# rizon-smd.net
KiCad netlist of a schematic drawn in EAGLE
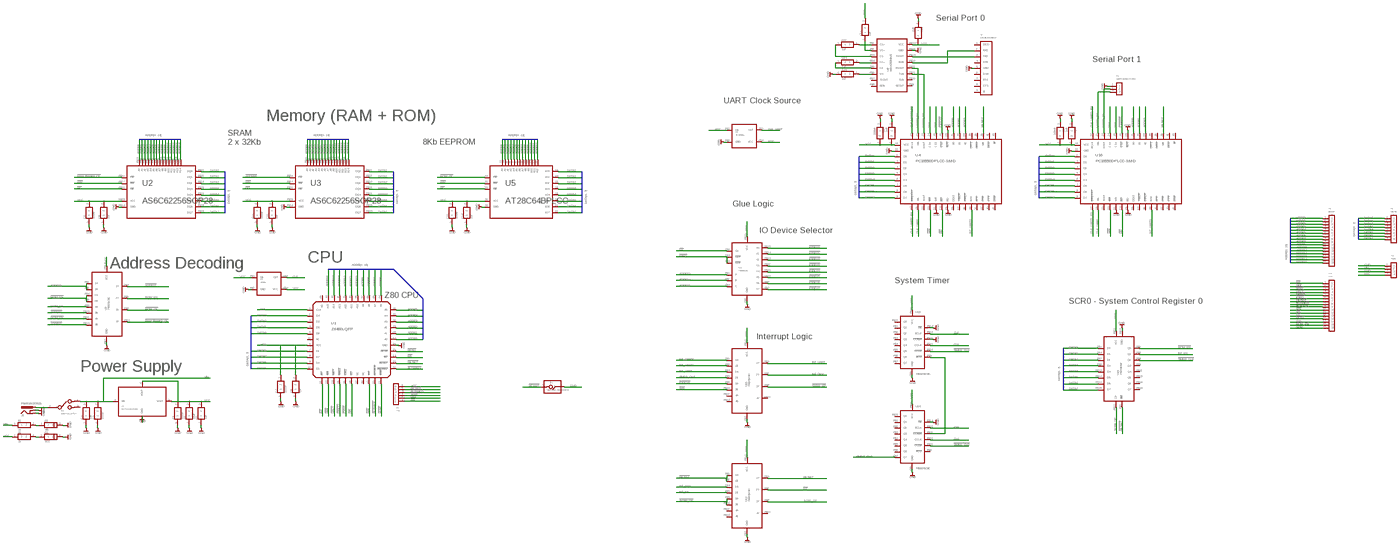
[diagram p0: schematic, sheet 1, overview]
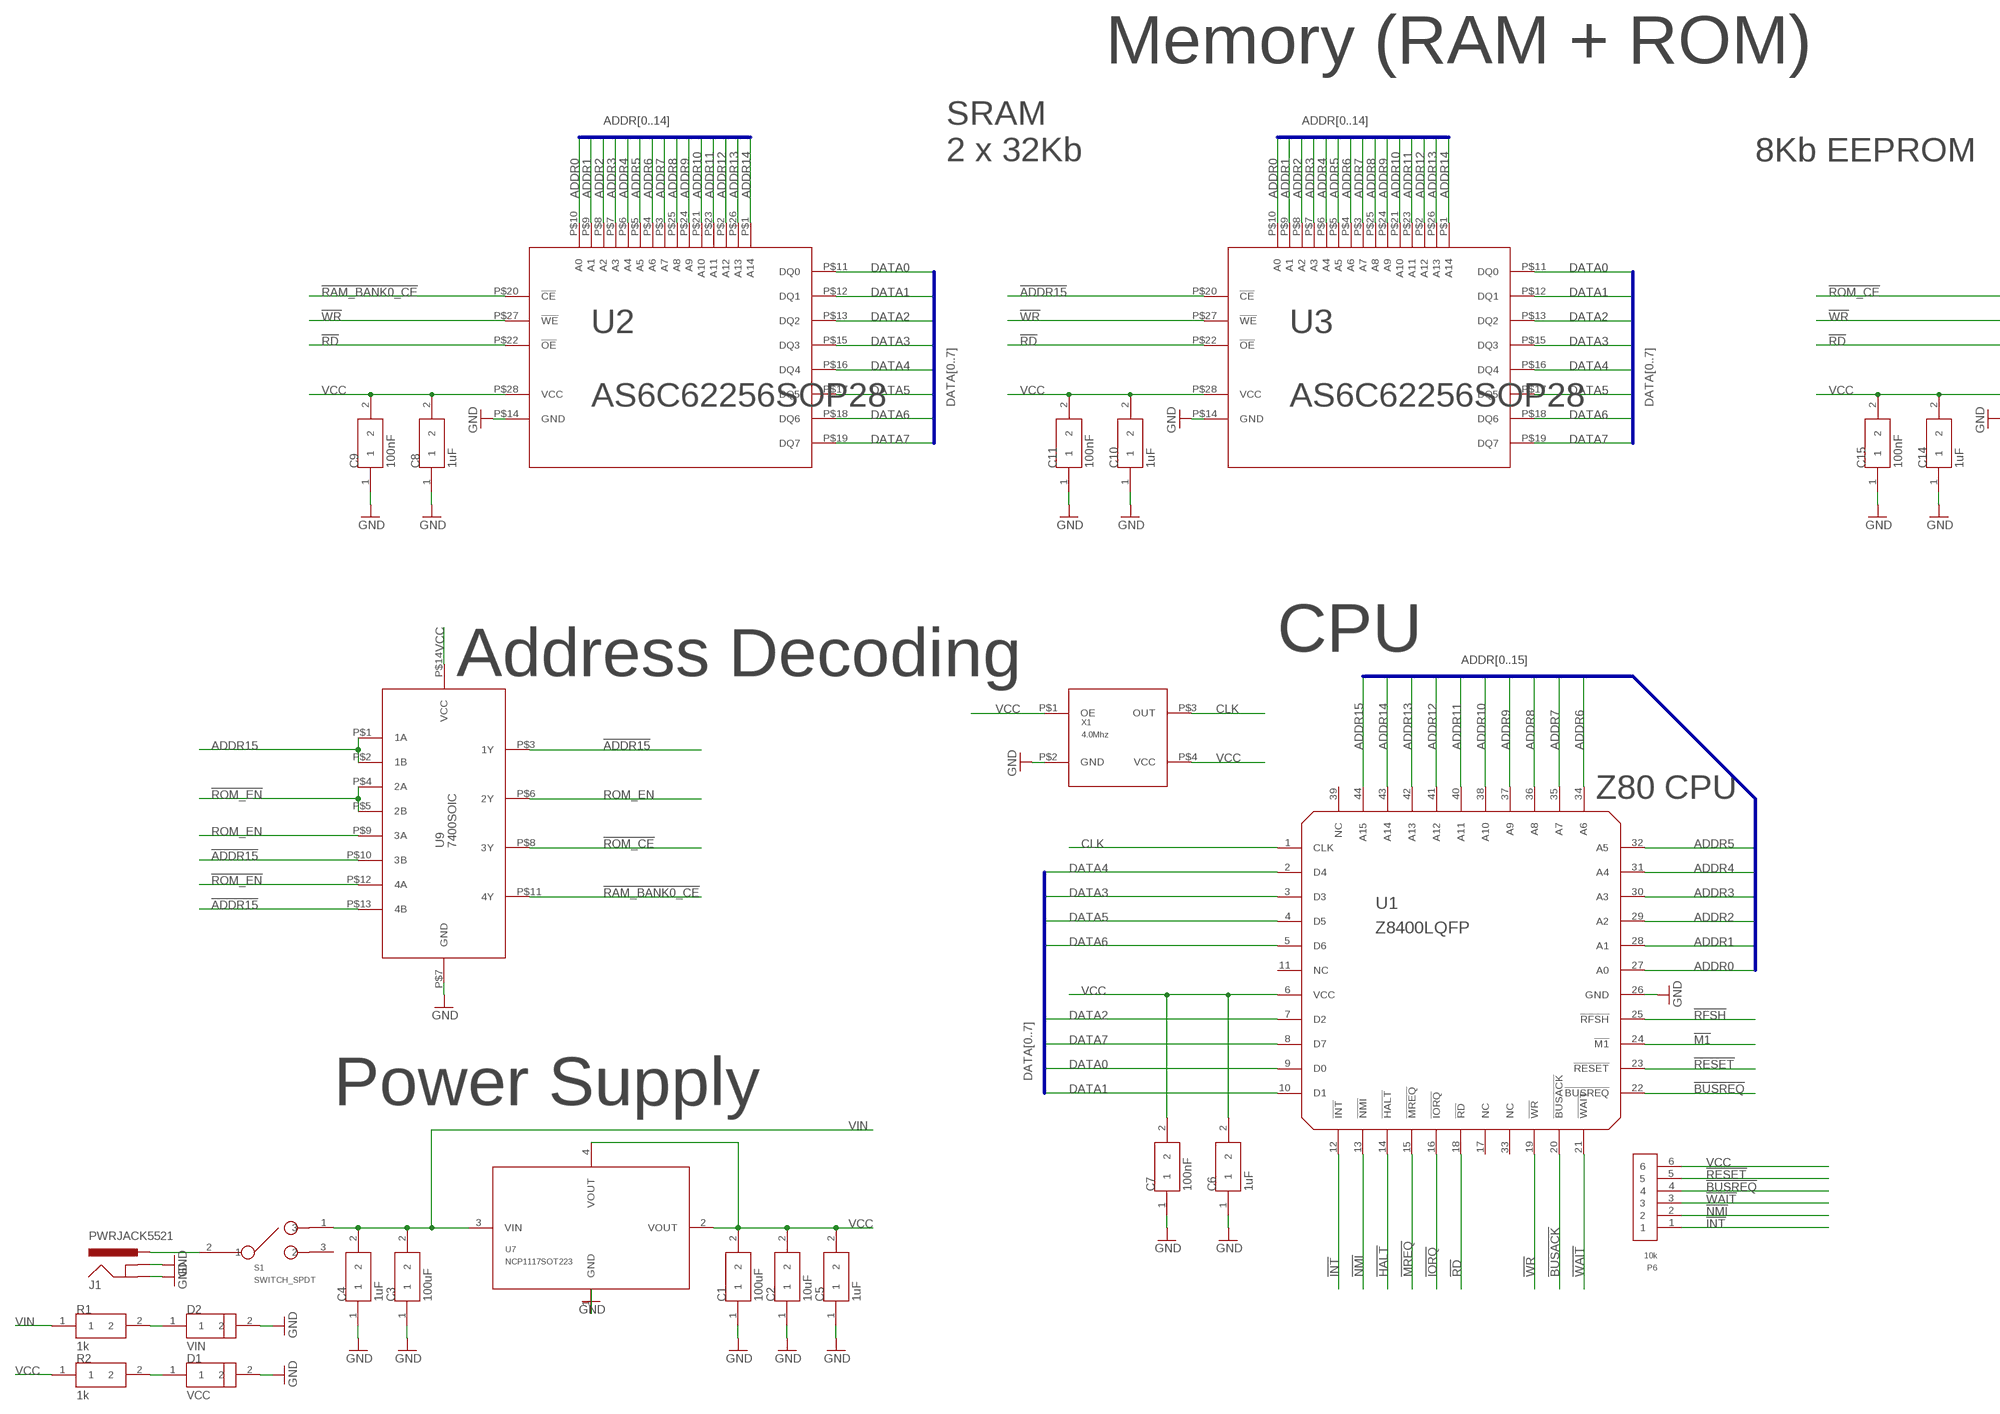
[diagram p1: schematic, sheet 1, part 1 of 4]
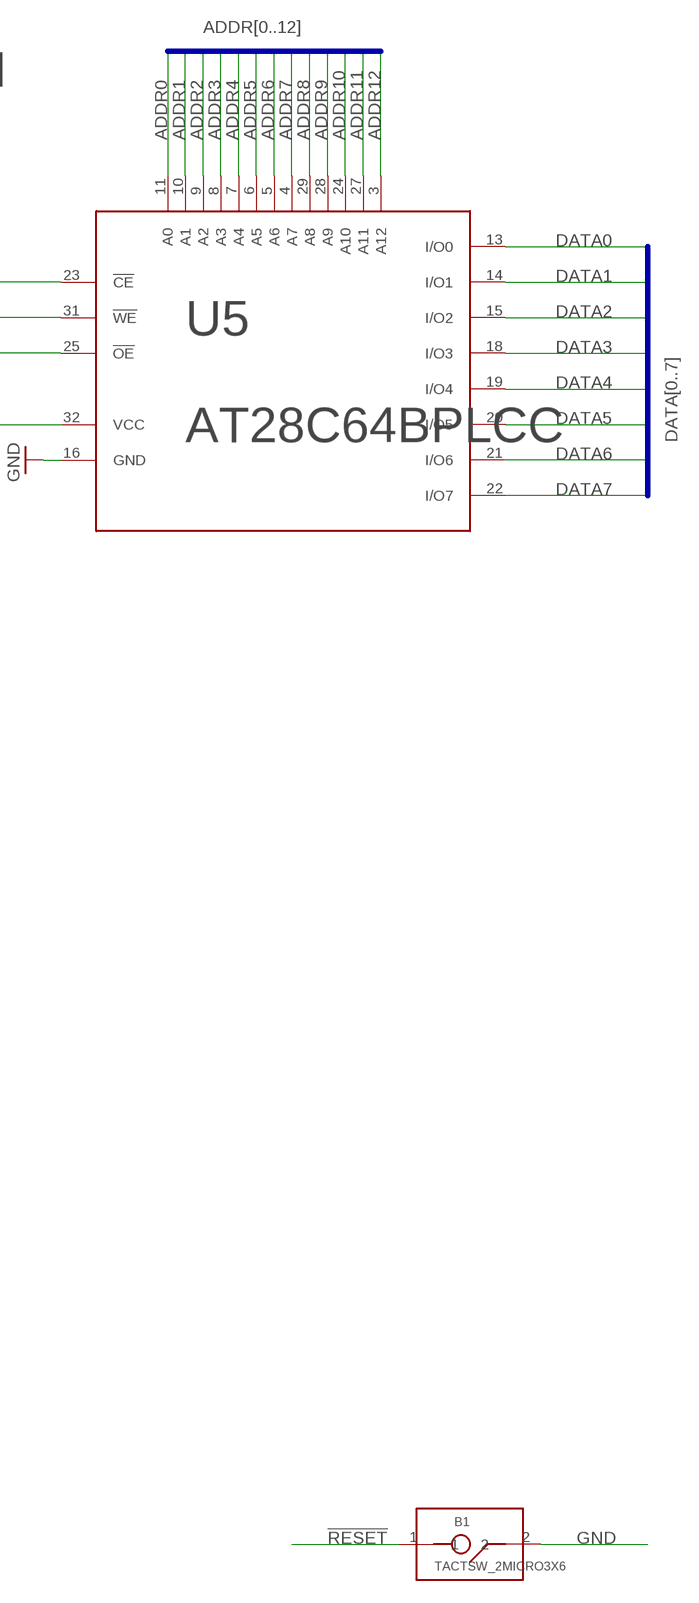
[diagram p2: schematic, sheet 1, part 2 of 4]
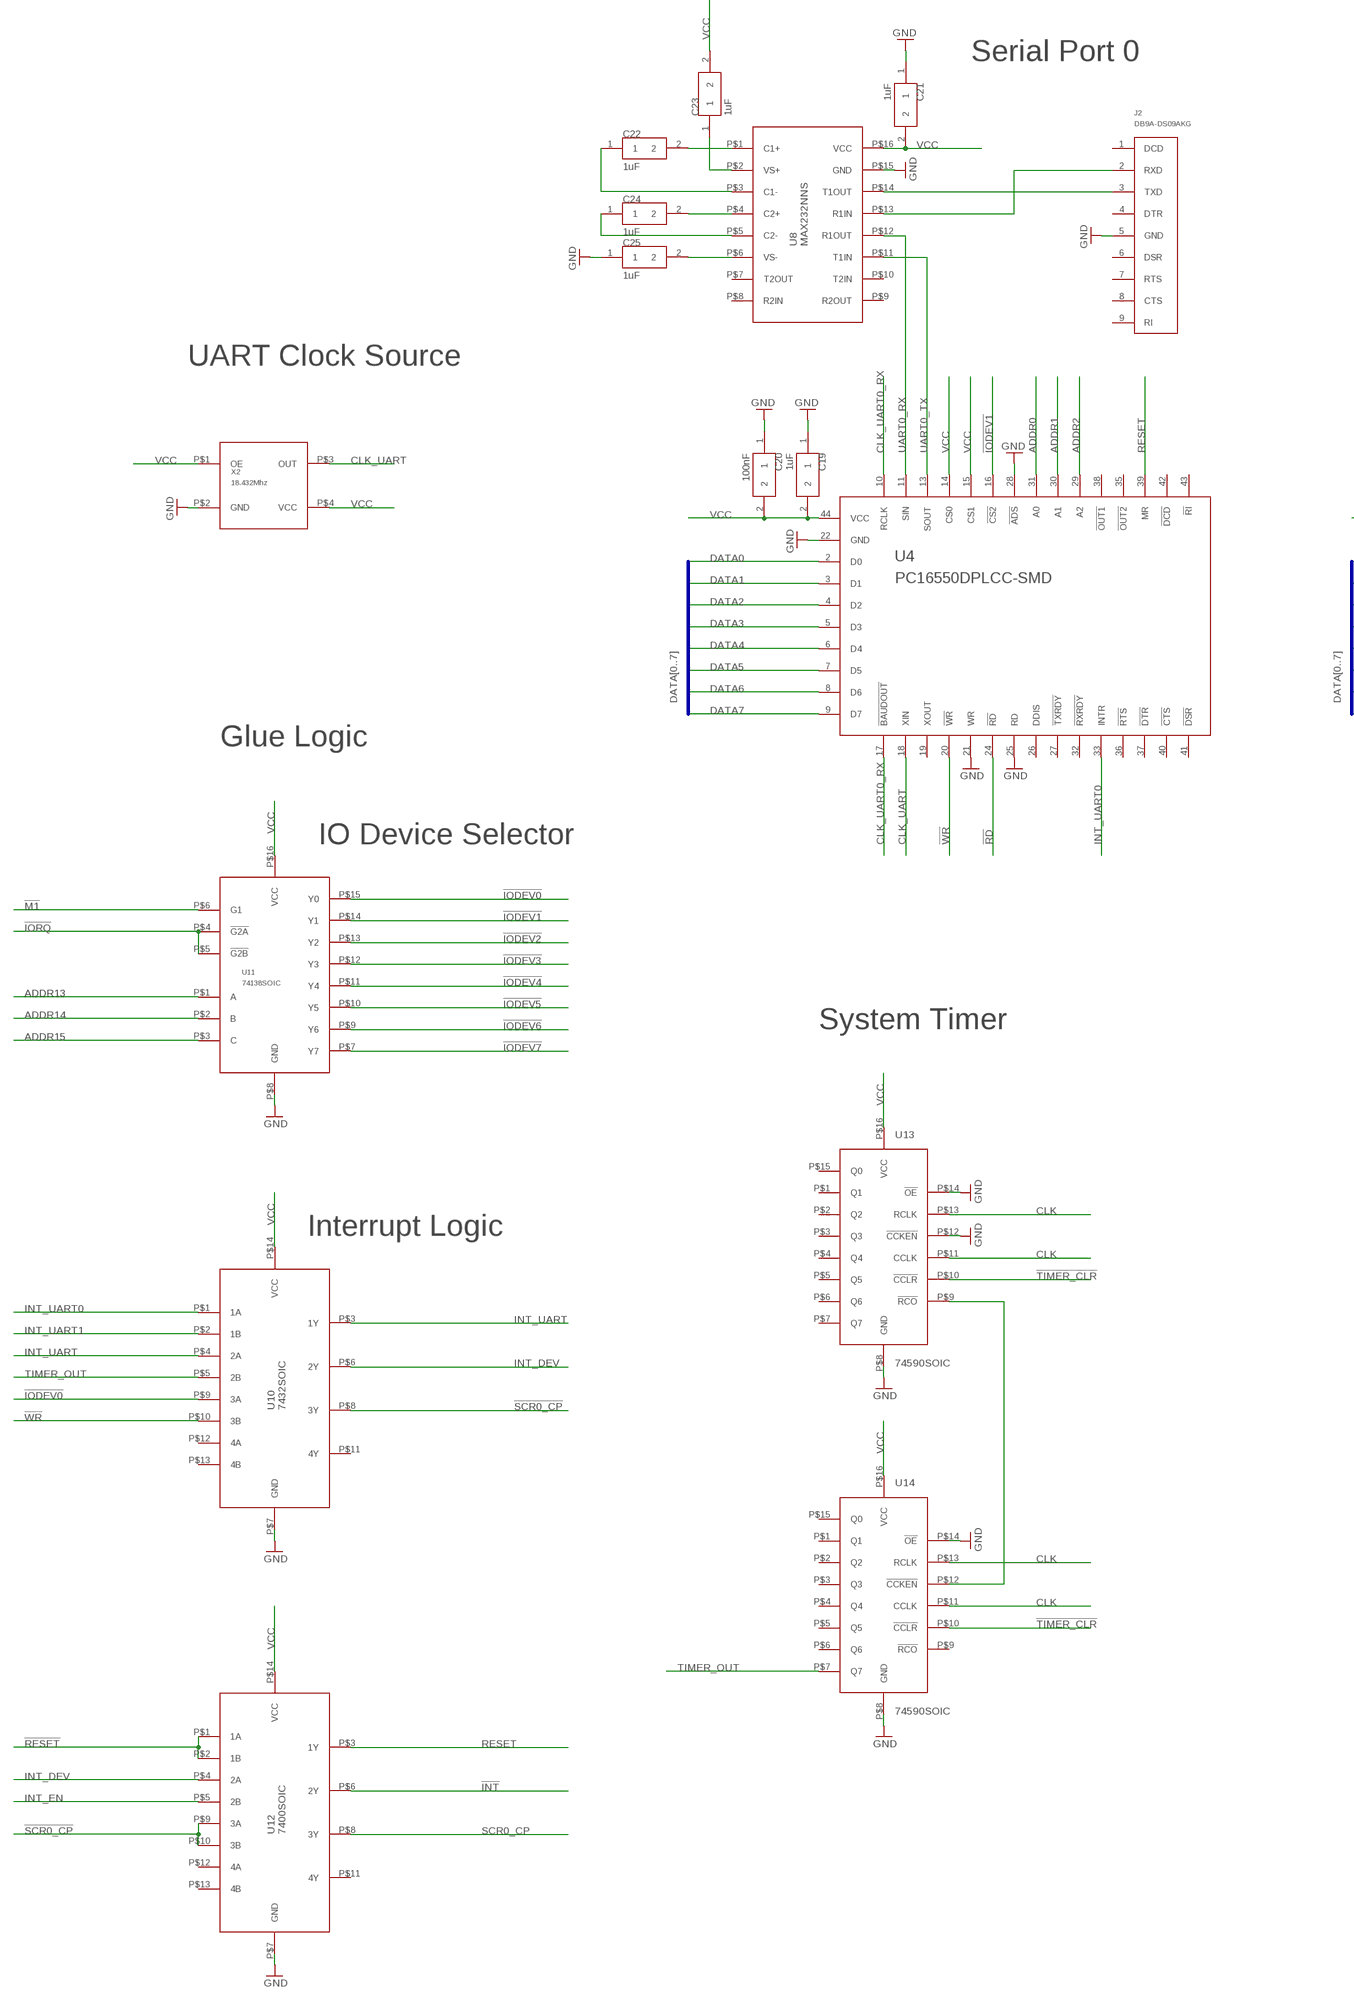
[diagram p3: schematic, sheet 1, part 3 of 4]
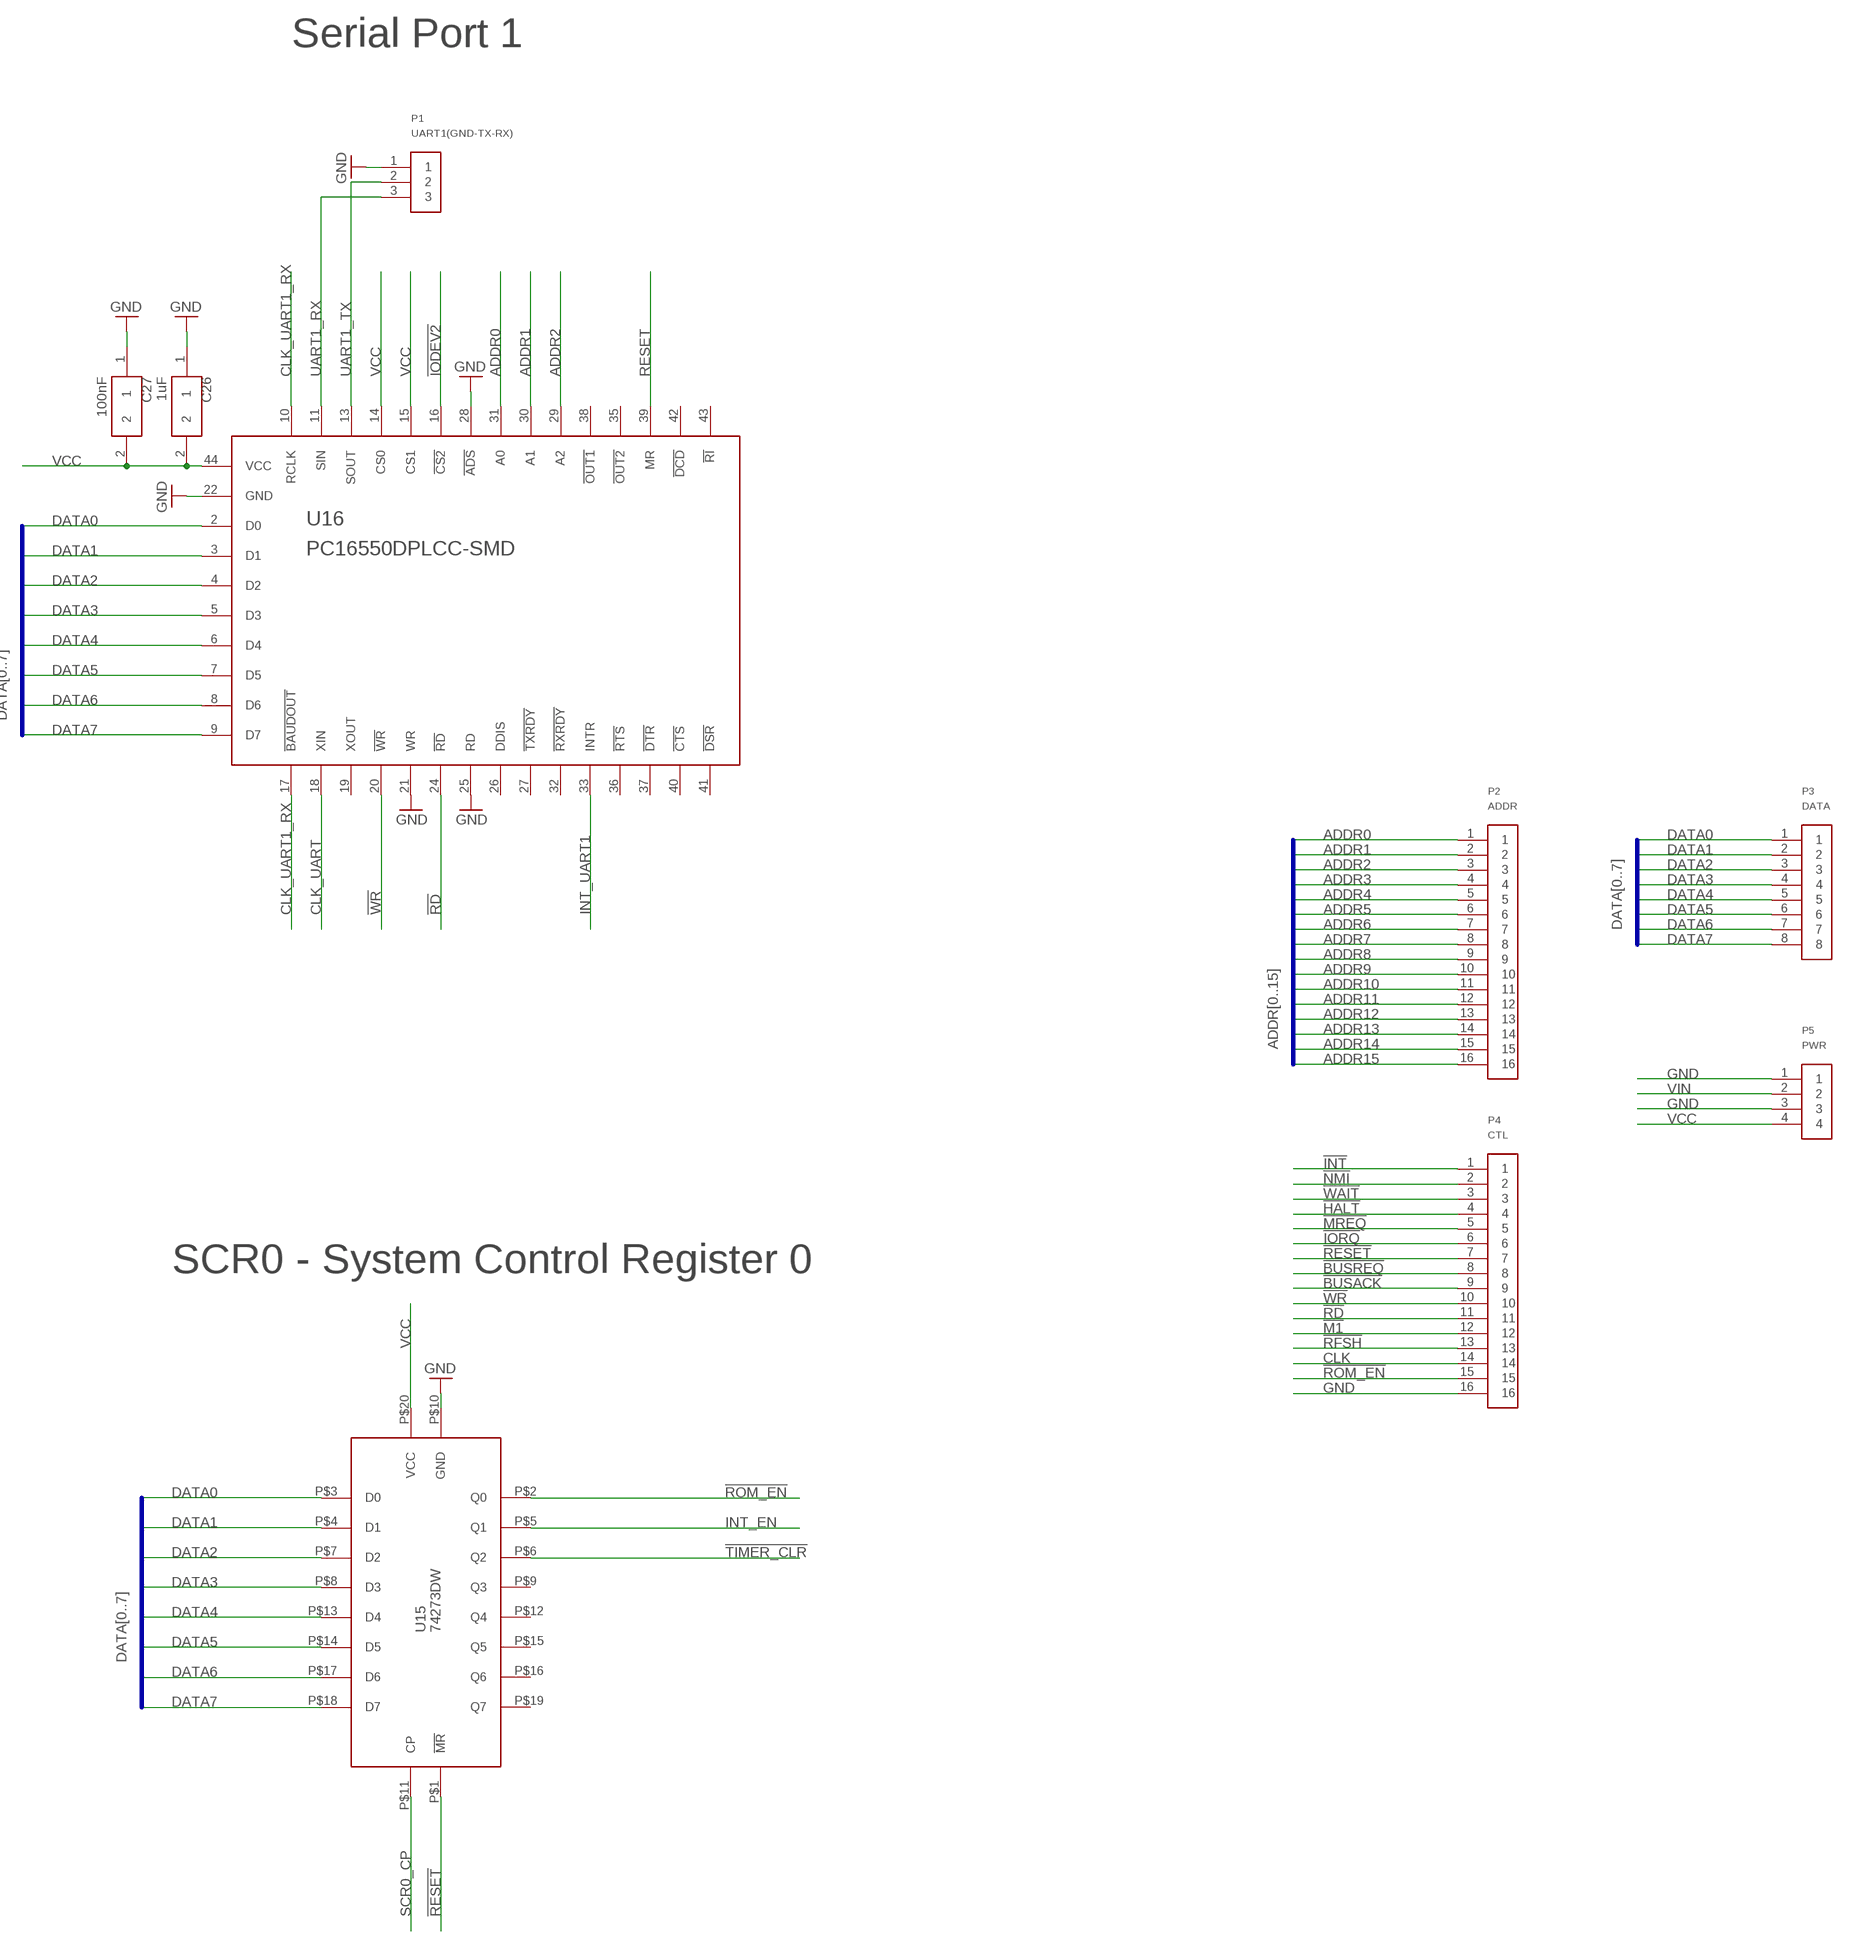
[diagram p4: schematic, sheet 1, part 4 of 4]

(export (version "E")
  (design (tool "Eeschema 10.0.6"))
  (components
    (comp (ref "B1")
      (value "TACTSW_2MICRO3X6")
      (footprint "eagle-import:TACTSW_MICRO3X6")
      (libsource (lib "eagle-import") (part "TACTSW_2MICRO3X6"))
    )
    (comp (ref "C1")
      (value "100uF")
      (footprint "eagle-import:1210")
      (libsource (lib "eagle-import") (part "CAP1210"))
    )
    (comp (ref "C2")
      (value "10uF")
      (footprint "eagle-import:0805")
      (libsource (lib "eagle-import") (part "CAP0805"))
    )
    (comp (ref "C3")
      (value "100uF")
      (footprint "eagle-import:1210")
      (libsource (lib "eagle-import") (part "CAP1210"))
    )
    (comp (ref "C4")
      (value "1uF")
      (footprint "eagle-import:0805")
      (libsource (lib "eagle-import") (part "CAP0805"))
    )
    (comp (ref "C5")
      (value "1uF")
      (footprint "eagle-import:0805")
      (libsource (lib "eagle-import") (part "CAP0805"))
    )
    (comp (ref "C6")
      (value "1uF")
      (footprint "eagle-import:0805")
      (libsource (lib "eagle-import") (part "CAP0805"))
    )
    (comp (ref "C7")
      (value "100nF")
      (footprint "eagle-import:0805")
      (libsource (lib "eagle-import") (part "CAP0805"))
    )
    (comp (ref "C8")
      (value "1uF")
      (footprint "eagle-import:0805")
      (libsource (lib "eagle-import") (part "CAP0805"))
    )
    (comp (ref "C9")
      (value "100nF")
      (footprint "eagle-import:0805")
      (libsource (lib "eagle-import") (part "CAP0805"))
    )
    (comp (ref "C10")
      (value "1uF")
      (footprint "eagle-import:0805")
      (libsource (lib "eagle-import") (part "CAP0805"))
    )
    (comp (ref "C11")
      (value "100nF")
      (footprint "eagle-import:0805")
      (libsource (lib "eagle-import") (part "CAP0805"))
    )
    (comp (ref "C14")
      (value "1uF")
      (footprint "eagle-import:0805")
      (libsource (lib "eagle-import") (part "CAP0805"))
    )
    (comp (ref "C15")
      (value "100nF")
      (footprint "eagle-import:0805")
      (libsource (lib "eagle-import") (part "CAP0805"))
    )
    (comp (ref "C19")
      (value "1uF")
      (footprint "eagle-import:0805")
      (libsource (lib "eagle-import") (part "CAP0805"))
    )
    (comp (ref "C20")
      (value "100nF")
      (footprint "eagle-import:0805")
      (libsource (lib "eagle-import") (part "CAP0805"))
    )
    (comp (ref "C21")
      (value "1uF")
      (footprint "eagle-import:0805")
      (libsource (lib "eagle-import") (part "CAP0805"))
    )
    (comp (ref "C22")
      (value "1uF")
      (footprint "eagle-import:0805")
      (libsource (lib "eagle-import") (part "CAP0805"))
    )
    (comp (ref "C23")
      (value "1uF")
      (footprint "eagle-import:0805")
      (libsource (lib "eagle-import") (part "CAP0805"))
    )
    (comp (ref "C24")
      (value "1uF")
      (footprint "eagle-import:0805")
      (libsource (lib "eagle-import") (part "CAP0805"))
    )
    (comp (ref "C25")
      (value "1uF")
      (footprint "eagle-import:0805")
      (libsource (lib "eagle-import") (part "CAP0805"))
    )
    (comp (ref "C26")
      (value "1uF")
      (footprint "eagle-import:0805")
      (libsource (lib "eagle-import") (part "CAP0805"))
    )
    (comp (ref "C27")
      (value "100nF")
      (footprint "eagle-import:0805")
      (libsource (lib "eagle-import") (part "CAP0805"))
    )
    (comp (ref "D1")
      (value "VCC")
      (footprint "eagle-import:0805")
      (libsource (lib "eagle-import") (part "LED0805"))
    )
    (comp (ref "D2")
      (value "VIN")
      (footprint "eagle-import:0805")
      (libsource (lib "eagle-import") (part "LED0805"))
    )
    (comp (ref "J1")
      (value "PWRJACK5521")
      (footprint "eagle-import:PWRJACK_5521")
      (libsource (lib "eagle-import") (part "PWRJACK5521"))
    )
    (comp (ref "J2")
      (value "DB9A-DS09AKG")
      (footprint "eagle-import:A-DS09AKG")
      (libsource (lib "eagle-import") (part "DB9A-DS09AKG"))
    )
    (comp (ref "P1")
      (value "UART1(GND-TX-RX)")
      (footprint "eagle-import:PIN_3")
      (libsource (lib "eagle-import") (part "PIN_3"))
    )
    (comp (ref "P2")
      (value "ADDR")
      (footprint "eagle-import:PIN_16")
      (libsource (lib "eagle-import") (part "PIN_16"))
    )
    (comp (ref "P3")
      (value "DATA")
      (footprint "eagle-import:PIN_8")
      (libsource (lib "eagle-import") (part "PIN_8"))
    )
    (comp (ref "P4")
      (value "CTL")
      (footprint "eagle-import:PIN_16")
      (libsource (lib "eagle-import") (part "PIN_16"))
    )
    (comp (ref "P5")
      (value "PWR")
      (footprint "eagle-import:PIN_4")
      (libsource (lib "eagle-import") (part "PIN_4"))
    )
    (comp (ref "P6")
      (value "10k")
      (footprint "eagle-import:PIN_6")
      (libsource (lib "eagle-import") (part "PIN_61LINE"))
    )
    (comp (ref "R1")
      (value "1k")
      (footprint "eagle-import:0805")
      (libsource (lib "eagle-import") (part "RES0805"))
    )
    (comp (ref "R2")
      (value "1k")
      (footprint "eagle-import:0805")
      (libsource (lib "eagle-import") (part "RES0805"))
    )
    (comp (ref "S1")
      (value "SWITCH_SPDT")
      (footprint "eagle-import:JS102011")
      (libsource (lib "eagle-import") (part "SWITCH_SPDT"))
    )
    (comp (ref "U1")
      (value "Z8400LQFP")
      (footprint "eagle-import:QFP44")
      (libsource (lib "eagle-import") (part "Z8400LQFP"))
    )
    (comp (ref "U2")
      (value "AS6C62256SOP28")
      (footprint "eagle-import:SOP28")
      (libsource (lib "eagle-import") (part "AS6C62256SOP28"))
    )
    (comp (ref "U3")
      (value "AS6C62256SOP28")
      (footprint "eagle-import:SOP28")
      (libsource (lib "eagle-import") (part "AS6C62256SOP28"))
    )
    (comp (ref "U4")
      (value "PC16550DPLCC-SMD")
      (footprint "eagle-import:PLCC44")
      (libsource (lib "eagle-import") (part "PC16550DPLCC-SMD"))
    )
    (comp (ref "U5")
      (value "AT28C64BPLCC")
      (footprint "eagle-import:PLCC-S32--SOCKET")
      (libsource (lib "eagle-import") (part "AT28C64BPLCC"))
    )
    (comp (ref "U7")
      (value "NCP1117SOT223")
      (footprint "eagle-import:SOT223")
      (libsource (lib "eagle-import") (part "NCP1117SOT223"))
    )
    (comp (ref "U8")
      (value "MAX232NNS")
      (footprint "eagle-import:SO16")
      (libsource (lib "eagle-import") (part "MAX232NNS"))
    )
    (comp (ref "U9")
      (value "7400SOIC")
      (footprint "eagle-import:SOIC14")
      (libsource (lib "eagle-import") (part "7400SOIC"))
    )
    (comp (ref "U10")
      (value "7432SOIC")
      (footprint "eagle-import:SOIC14")
      (libsource (lib "eagle-import") (part "7432SOIC"))
    )
    (comp (ref "U11")
      (value "74138SOIC")
      (footprint "eagle-import:SOIC16")
      (libsource (lib "eagle-import") (part "74138SOIC"))
    )
    (comp (ref "U12")
      (value "7400SOIC")
      (footprint "eagle-import:SOIC14")
      (libsource (lib "eagle-import") (part "7400SOIC"))
    )
    (comp (ref "U13")
      (value "74590SOIC")
      (footprint "eagle-import:SOIC16")
      (libsource (lib "eagle-import") (part "74590SOIC"))
    )
    (comp (ref "U14")
      (value "74590SOIC")
      (footprint "eagle-import:SOIC16")
      (libsource (lib "eagle-import") (part "74590SOIC"))
    )
    (comp (ref "U15")
      (value "74273DW")
      (footprint "eagle-import:SO20")
      (libsource (lib "eagle-import") (part "74273DW"))
    )
    (comp (ref "U16")
      (value "PC16550DPLCC-SMD")
      (footprint "eagle-import:PLCC44")
      (libsource (lib "eagle-import") (part "PC16550DPLCC-SMD"))
    )
    (comp (ref "X1")
      (value "4.0Mhz")
      (footprint "eagle-import:OSC4-SMD-7X5")
      (libsource (lib "eagle-import") (part "OSC4_OESMD-7X5"))
    )
    (comp (ref "X2")
      (value "18.432Mhz")
      (footprint "eagle-import:OSC4-SMD-7X5")
      (libsource (lib "eagle-import") (part "OSC4_OESMD-7X5"))
    )
  )
  (nets
    (net (code "1") (name "/ADDR0") (class "Default")
      (node (ref "P2") (pin "1") (pinfunction "1_1") (pintype "bidirectional"))
      (node (ref "U1") (pin "27") (pinfunction "A0_27") (pintype "bidirectional"))
      (node (ref "U16") (pin "31") (pinfunction "A0_31") (pintype "bidirectional"))
      (node (ref "U2") (pin "P$10") (pinfunction "A0_P$10") (pintype "bidirectional"))
      (node (ref "U3") (pin "P$10") (pinfunction "A0_P$10") (pintype "bidirectional"))
      (node (ref "U4") (pin "31") (pinfunction "A0_31") (pintype "bidirectional"))
      (node (ref "U5") (pin "11") (pinfunction "A0_11") (pintype "bidirectional"))
    )
    (net (code "2") (name "/ADDR1") (class "Default")
      (node (ref "P2") (pin "2") (pinfunction "2_2") (pintype "bidirectional"))
      (node (ref "U1") (pin "28") (pinfunction "A1_28") (pintype "bidirectional"))
      (node (ref "U16") (pin "30") (pinfunction "A1_30") (pintype "bidirectional"))
      (node (ref "U2") (pin "P$9") (pinfunction "A1_P$9") (pintype "bidirectional"))
      (node (ref "U3") (pin "P$9") (pinfunction "A1_P$9") (pintype "bidirectional"))
      (node (ref "U4") (pin "30") (pinfunction "A1_30") (pintype "bidirectional"))
      (node (ref "U5") (pin "10") (pinfunction "A1_10") (pintype "bidirectional"))
    )
    (net (code "3") (name "/ADDR2") (class "Default")
      (node (ref "P2") (pin "3") (pinfunction "3_3") (pintype "bidirectional"))
      (node (ref "U1") (pin "29") (pinfunction "A2_29") (pintype "bidirectional"))
      (node (ref "U16") (pin "29") (pinfunction "A2_29") (pintype "bidirectional"))
      (node (ref "U2") (pin "P$8") (pinfunction "A2_P$8") (pintype "bidirectional"))
      (node (ref "U3") (pin "P$8") (pinfunction "A2_P$8") (pintype "bidirectional"))
      (node (ref "U4") (pin "29") (pinfunction "A2_29") (pintype "bidirectional"))
      (node (ref "U5") (pin "9") (pinfunction "A2_9") (pintype "bidirectional"))
    )
    (net (code "4") (name "/ADDR3") (class "Default")
      (node (ref "P2") (pin "4") (pinfunction "4_4") (pintype "bidirectional"))
      (node (ref "U1") (pin "30") (pinfunction "A3_30") (pintype "bidirectional"))
      (node (ref "U2") (pin "P$7") (pinfunction "A3_P$7") (pintype "bidirectional"))
      (node (ref "U3") (pin "P$7") (pinfunction "A3_P$7") (pintype "bidirectional"))
      (node (ref "U5") (pin "8") (pinfunction "A3_8") (pintype "bidirectional"))
    )
    (net (code "5") (name "/ADDR4") (class "Default")
      (node (ref "P2") (pin "5") (pinfunction "5_5") (pintype "bidirectional"))
      (node (ref "U1") (pin "31") (pinfunction "A4_31") (pintype "bidirectional"))
      (node (ref "U2") (pin "P$6") (pinfunction "A4_P$6") (pintype "bidirectional"))
      (node (ref "U3") (pin "P$6") (pinfunction "A4_P$6") (pintype "bidirectional"))
      (node (ref "U5") (pin "7") (pinfunction "A4_7") (pintype "bidirectional"))
    )
    (net (code "6") (name "/ADDR5") (class "Default")
      (node (ref "P2") (pin "6") (pinfunction "6_6") (pintype "bidirectional"))
      (node (ref "U1") (pin "32") (pinfunction "A5_32") (pintype "bidirectional"))
      (node (ref "U2") (pin "P$5") (pinfunction "A5_P$5") (pintype "bidirectional"))
      (node (ref "U3") (pin "P$5") (pinfunction "A5_P$5") (pintype "bidirectional"))
      (node (ref "U5") (pin "6") (pinfunction "A5_6") (pintype "bidirectional"))
    )
    (net (code "7") (name "/ADDR6") (class "Default")
      (node (ref "P2") (pin "7") (pinfunction "7_7") (pintype "bidirectional"))
      (node (ref "U1") (pin "34") (pinfunction "A6_34") (pintype "bidirectional"))
      (node (ref "U2") (pin "P$4") (pinfunction "A6_P$4") (pintype "bidirectional"))
      (node (ref "U3") (pin "P$4") (pinfunction "A6_P$4") (pintype "bidirectional"))
      (node (ref "U5") (pin "5") (pinfunction "A6_5") (pintype "bidirectional"))
    )
    (net (code "8") (name "/ADDR7") (class "Default")
      (node (ref "P2") (pin "8") (pinfunction "8_8") (pintype "bidirectional"))
      (node (ref "U1") (pin "35") (pinfunction "A7_35") (pintype "bidirectional"))
      (node (ref "U2") (pin "P$3") (pinfunction "A7_P$3") (pintype "bidirectional"))
      (node (ref "U3") (pin "P$3") (pinfunction "A7_P$3") (pintype "bidirectional"))
      (node (ref "U5") (pin "4") (pinfunction "A7_4") (pintype "bidirectional"))
    )
    (net (code "9") (name "/ADDR8") (class "Default")
      (node (ref "P2") (pin "9") (pinfunction "9_9") (pintype "bidirectional"))
      (node (ref "U1") (pin "36") (pinfunction "A8_36") (pintype "bidirectional"))
      (node (ref "U2") (pin "P$25") (pinfunction "A8_P$25") (pintype "bidirectional"))
      (node (ref "U3") (pin "P$25") (pinfunction "A8_P$25") (pintype "bidirectional"))
      (node (ref "U5") (pin "29") (pinfunction "A8_29") (pintype "bidirectional"))
    )
    (net (code "10") (name "/ADDR9") (class "Default")
      (node (ref "P2") (pin "10") (pinfunction "10_10") (pintype "bidirectional"))
      (node (ref "U1") (pin "37") (pinfunction "A9_37") (pintype "bidirectional"))
      (node (ref "U2") (pin "P$24") (pinfunction "A9_P$24") (pintype "bidirectional"))
      (node (ref "U3") (pin "P$24") (pinfunction "A9_P$24") (pintype "bidirectional"))
      (node (ref "U5") (pin "28") (pinfunction "A9_28") (pintype "bidirectional"))
    )
    (net (code "11") (name "/ADDR10") (class "Default")
      (node (ref "P2") (pin "11") (pinfunction "11_11") (pintype "bidirectional"))
      (node (ref "U1") (pin "38") (pinfunction "A10_38") (pintype "bidirectional"))
      (node (ref "U2") (pin "P$21") (pinfunction "A10_P$21") (pintype "bidirectional"))
      (node (ref "U3") (pin "P$21") (pinfunction "A10_P$21") (pintype "bidirectional"))
      (node (ref "U5") (pin "24") (pinfunction "A10_24") (pintype "bidirectional"))
    )
    (net (code "12") (name "/ADDR11") (class "Default")
      (node (ref "P2") (pin "12") (pinfunction "12_12") (pintype "bidirectional"))
      (node (ref "U1") (pin "40") (pinfunction "A11_40") (pintype "bidirectional"))
      (node (ref "U2") (pin "P$23") (pinfunction "A11_P$23") (pintype "bidirectional"))
      (node (ref "U3") (pin "P$23") (pinfunction "A11_P$23") (pintype "bidirectional"))
      (node (ref "U5") (pin "27") (pinfunction "A11_27") (pintype "bidirectional"))
    )
    (net (code "13") (name "/ADDR12") (class "Default")
      (node (ref "P2") (pin "13") (pinfunction "13_13") (pintype "bidirectional"))
      (node (ref "U1") (pin "41") (pinfunction "A12_41") (pintype "bidirectional"))
      (node (ref "U2") (pin "P$2") (pinfunction "A12_P$2") (pintype "bidirectional"))
      (node (ref "U3") (pin "P$2") (pinfunction "A12_P$2") (pintype "bidirectional"))
      (node (ref "U5") (pin "3") (pinfunction "A12_3") (pintype "bidirectional"))
    )
    (net (code "14") (name "/ADDR13") (class "Default")
      (node (ref "P2") (pin "14") (pinfunction "14_14") (pintype "bidirectional"))
      (node (ref "U1") (pin "42") (pinfunction "A13_42") (pintype "bidirectional"))
      (node (ref "U11") (pin "P$1") (pinfunction "A_P$1") (pintype "bidirectional"))
      (node (ref "U2") (pin "P$26") (pinfunction "A13_P$26") (pintype "bidirectional"))
      (node (ref "U3") (pin "P$26") (pinfunction "A13_P$26") (pintype "bidirectional"))
    )
    (net (code "15") (name "/ADDR14") (class "Default")
      (node (ref "P2") (pin "15") (pinfunction "15_15") (pintype "bidirectional"))
      (node (ref "U1") (pin "43") (pinfunction "A14_43") (pintype "bidirectional"))
      (node (ref "U11") (pin "P$2") (pinfunction "B_P$2") (pintype "bidirectional"))
      (node (ref "U2") (pin "P$1") (pinfunction "A14_P$1") (pintype "bidirectional"))
      (node (ref "U3") (pin "P$1") (pinfunction "A14_P$1") (pintype "bidirectional"))
    )
    (net (code "16") (name "/ADDR15") (class "Default")
      (node (ref "P2") (pin "16") (pinfunction "16_16") (pintype "bidirectional"))
      (node (ref "U1") (pin "44") (pinfunction "A15_44") (pintype "bidirectional"))
      (node (ref "U11") (pin "P$3") (pinfunction "C_P$3") (pintype "bidirectional"))
      (node (ref "U9") (pin "P$1") (pinfunction "1A_P$1") (pintype "bidirectional"))
      (node (ref "U9") (pin "P$2") (pinfunction "1B_P$2") (pintype "bidirectional"))
    )
    (net (code "20") (name "/CLK") (class "Default")
      (node (ref "P4") (pin "14") (pinfunction "14_14") (pintype "bidirectional"))
      (node (ref "U1") (pin "1") (pinfunction "CLK_1") (pintype "bidirectional"))
      (node (ref "U13") (pin "P$11") (pinfunction "CCLK_P$11") (pintype "bidirectional"))
      (node (ref "U13") (pin "P$13") (pinfunction "RCLK_P$13") (pintype "bidirectional"))
      (node (ref "U14") (pin "P$11") (pinfunction "CCLK_P$11") (pintype "bidirectional"))
      (node (ref "U14") (pin "P$13") (pinfunction "RCLK_P$13") (pintype "bidirectional"))
      (node (ref "X1") (pin "P$3") (pinfunction "OUT_P$3") (pintype "bidirectional"))
    )
    (net (code "21") (name "/CLK_UART") (class "Default")
      (node (ref "U16") (pin "18") (pinfunction "XIN_18") (pintype "bidirectional"))
      (node (ref "U4") (pin "18") (pinfunction "XIN_18") (pintype "bidirectional"))
      (node (ref "X2") (pin "P$3") (pinfunction "OUT_P$3") (pintype "bidirectional"))
    )
    (net (code "22") (name "/CLK_UART0_RX") (class "Default")
      (node (ref "U4") (pin "10") (pinfunction "RCLK_10") (pintype "bidirectional"))
      (node (ref "U4") (pin "17") (pinfunction "~{BAUDOUT}_17") (pintype "bidirectional"))
    )
    (net (code "23") (name "/CLK_UART1_RX") (class "Default")
      (node (ref "U16") (pin "10") (pinfunction "RCLK_10") (pintype "bidirectional"))
      (node (ref "U16") (pin "17") (pinfunction "~{BAUDOUT}_17") (pintype "bidirectional"))
    )
    (net (code "24") (name "/DATA0") (class "Default")
      (node (ref "P3") (pin "1") (pinfunction "1_1") (pintype "bidirectional"))
      (node (ref "U1") (pin "9") (pinfunction "D0_9") (pintype "bidirectional"))
      (node (ref "U15") (pin "P$3") (pinfunction "D0_P$3") (pintype "bidirectional"))
      (node (ref "U16") (pin "2") (pinfunction "D0_2") (pintype "bidirectional"))
      (node (ref "U2") (pin "P$11") (pinfunction "DQ0_P$11") (pintype "bidirectional"))
      (node (ref "U3") (pin "P$11") (pinfunction "DQ0_P$11") (pintype "bidirectional"))
      (node (ref "U4") (pin "2") (pinfunction "D0_2") (pintype "bidirectional"))
      (node (ref "U5") (pin "13") (pinfunction "I/O0_13") (pintype "bidirectional"))
    )
    (net (code "25") (name "/DATA1") (class "Default")
      (node (ref "P3") (pin "2") (pinfunction "2_2") (pintype "bidirectional"))
      (node (ref "U1") (pin "10") (pinfunction "D1_10") (pintype "bidirectional"))
      (node (ref "U15") (pin "P$4") (pinfunction "D1_P$4") (pintype "bidirectional"))
      (node (ref "U16") (pin "3") (pinfunction "D1_3") (pintype "bidirectional"))
      (node (ref "U2") (pin "P$12") (pinfunction "DQ1_P$12") (pintype "bidirectional"))
      (node (ref "U3") (pin "P$12") (pinfunction "DQ1_P$12") (pintype "bidirectional"))
      (node (ref "U4") (pin "3") (pinfunction "D1_3") (pintype "bidirectional"))
      (node (ref "U5") (pin "14") (pinfunction "I/O1_14") (pintype "bidirectional"))
    )
    (net (code "26") (name "/DATA2") (class "Default")
      (node (ref "P3") (pin "3") (pinfunction "3_3") (pintype "bidirectional"))
      (node (ref "U1") (pin "7") (pinfunction "D2_7") (pintype "bidirectional"))
      (node (ref "U15") (pin "P$7") (pinfunction "D2_P$7") (pintype "bidirectional"))
      (node (ref "U16") (pin "4") (pinfunction "D2_4") (pintype "bidirectional"))
      (node (ref "U2") (pin "P$13") (pinfunction "DQ2_P$13") (pintype "bidirectional"))
      (node (ref "U3") (pin "P$13") (pinfunction "DQ2_P$13") (pintype "bidirectional"))
      (node (ref "U4") (pin "4") (pinfunction "D2_4") (pintype "bidirectional"))
      (node (ref "U5") (pin "15") (pinfunction "I/O2_15") (pintype "bidirectional"))
    )
    (net (code "27") (name "/DATA3") (class "Default")
      (node (ref "P3") (pin "4") (pinfunction "4_4") (pintype "bidirectional"))
      (node (ref "U1") (pin "3") (pinfunction "D3_3") (pintype "bidirectional"))
      (node (ref "U15") (pin "P$8") (pinfunction "D3_P$8") (pintype "bidirectional"))
      (node (ref "U16") (pin "5") (pinfunction "D3_5") (pintype "bidirectional"))
      (node (ref "U2") (pin "P$15") (pinfunction "DQ3_P$15") (pintype "bidirectional"))
      (node (ref "U3") (pin "P$15") (pinfunction "DQ3_P$15") (pintype "bidirectional"))
      (node (ref "U4") (pin "5") (pinfunction "D3_5") (pintype "bidirectional"))
      (node (ref "U5") (pin "18") (pinfunction "I/O3_18") (pintype "bidirectional"))
    )
    (net (code "28") (name "/DATA4") (class "Default")
      (node (ref "P3") (pin "5") (pinfunction "5_5") (pintype "bidirectional"))
      (node (ref "U1") (pin "2") (pinfunction "D4_2") (pintype "bidirectional"))
      (node (ref "U15") (pin "P$13") (pinfunction "D4_P$13") (pintype "bidirectional"))
      (node (ref "U16") (pin "6") (pinfunction "D4_6") (pintype "bidirectional"))
      (node (ref "U2") (pin "P$16") (pinfunction "DQ4_P$16") (pintype "bidirectional"))
      (node (ref "U3") (pin "P$16") (pinfunction "DQ4_P$16") (pintype "bidirectional"))
      (node (ref "U4") (pin "6") (pinfunction "D4_6") (pintype "bidirectional"))
      (node (ref "U5") (pin "19") (pinfunction "I/O4_19") (pintype "bidirectional"))
    )
    (net (code "29") (name "/DATA5") (class "Default")
      (node (ref "P3") (pin "6") (pinfunction "6_6") (pintype "bidirectional"))
      (node (ref "U1") (pin "4") (pinfunction "D5_4") (pintype "bidirectional"))
      (node (ref "U15") (pin "P$14") (pinfunction "D5_P$14") (pintype "bidirectional"))
      (node (ref "U16") (pin "7") (pinfunction "D5_7") (pintype "bidirectional"))
      (node (ref "U2") (pin "P$17") (pinfunction "DQ5_P$17") (pintype "bidirectional"))
      (node (ref "U3") (pin "P$17") (pinfunction "DQ5_P$17") (pintype "bidirectional"))
      (node (ref "U4") (pin "7") (pinfunction "D5_7") (pintype "bidirectional"))
      (node (ref "U5") (pin "20") (pinfunction "I/O5_20") (pintype "bidirectional"))
    )
    (net (code "30") (name "/DATA6") (class "Default")
      (node (ref "P3") (pin "7") (pinfunction "7_7") (pintype "bidirectional"))
      (node (ref "U1") (pin "5") (pinfunction "D6_5") (pintype "bidirectional"))
      (node (ref "U15") (pin "P$17") (pinfunction "D6_P$17") (pintype "bidirectional"))
      (node (ref "U16") (pin "8") (pinfunction "D6_8") (pintype "bidirectional"))
      (node (ref "U2") (pin "P$18") (pinfunction "DQ6_P$18") (pintype "bidirectional"))
      (node (ref "U3") (pin "P$18") (pinfunction "DQ6_P$18") (pintype "bidirectional"))
      (node (ref "U4") (pin "8") (pinfunction "D6_8") (pintype "bidirectional"))
      (node (ref "U5") (pin "21") (pinfunction "I/O6_21") (pintype "bidirectional"))
    )
    (net (code "31") (name "/DATA7") (class "Default")
      (node (ref "P3") (pin "8") (pinfunction "8_8") (pintype "bidirectional"))
      (node (ref "U1") (pin "8") (pinfunction "D7_8") (pintype "bidirectional"))
      (node (ref "U15") (pin "P$18") (pinfunction "D7_P$18") (pintype "bidirectional"))
      (node (ref "U16") (pin "9") (pinfunction "D7_9") (pintype "bidirectional"))
      (node (ref "U2") (pin "P$19") (pinfunction "DQ7_P$19") (pintype "bidirectional"))
      (node (ref "U3") (pin "P$19") (pinfunction "DQ7_P$19") (pintype "bidirectional"))
      (node (ref "U4") (pin "9") (pinfunction "D7_9") (pintype "bidirectional"))
      (node (ref "U5") (pin "22") (pinfunction "I/O7_22") (pintype "bidirectional"))
    )
    (net (code "33") (name "/INT_DEV") (class "Default")
      (node (ref "U10") (pin "P$6") (pinfunction "2Y_P$6") (pintype "bidirectional"))
      (node (ref "U12") (pin "P$4") (pinfunction "2A_P$4") (pintype "bidirectional"))
    )
    (net (code "34") (name "/INT_EN") (class "Default")
      (node (ref "U12") (pin "P$5") (pinfunction "2B_P$5") (pintype "bidirectional"))
      (node (ref "U15") (pin "P$5") (pinfunction "Q1_P$5") (pintype "bidirectional"))
    )
    (net (code "35") (name "/INT_UART") (class "Default")
      (node (ref "U10") (pin "P$3") (pinfunction "1Y_P$3") (pintype "bidirectional"))
      (node (ref "U10") (pin "P$4") (pinfunction "2A_P$4") (pintype "bidirectional"))
    )
    (net (code "36") (name "/INT_UART0") (class "Default")
      (node (ref "U10") (pin "P$1") (pinfunction "1A_P$1") (pintype "bidirectional"))
      (node (ref "U4") (pin "33") (pinfunction "INTR_33") (pintype "bidirectional"))
    )
    (net (code "37") (name "/INT_UART1") (class "Default")
      (node (ref "U10") (pin "P$2") (pinfunction "1B_P$2") (pintype "bidirectional"))
      (node (ref "U16") (pin "33") (pinfunction "INTR_33") (pintype "bidirectional"))
    )
    (net (code "38") (name "/RESET") (class "Default")
      (node (ref "U12") (pin "P$3") (pinfunction "1Y_P$3") (pintype "bidirectional"))
      (node (ref "U16") (pin "39") (pinfunction "MR_39") (pintype "bidirectional"))
      (node (ref "U4") (pin "39") (pinfunction "MR_39") (pintype "bidirectional"))
    )
    (net (code "39") (name "/ROM_EN") (class "Default")
      (node (ref "U9") (pin "P$6") (pinfunction "2Y_P$6") (pintype "bidirectional"))
      (node (ref "U9") (pin "P$9") (pinfunction "3A_P$9") (pintype "bidirectional"))
    )
    (net (code "40") (name "/SCR0_CP") (class "Default")
      (node (ref "U12") (pin "P$8") (pinfunction "3Y_P$8") (pintype "bidirectional"))
      (node (ref "U15") (pin "P$11") (pinfunction "CP_P$11") (pintype "bidirectional"))
    )
    (net (code "41") (name "/TIMER_OUT") (class "Default")
      (node (ref "U10") (pin "P$5") (pinfunction "2B_P$5") (pintype "bidirectional"))
      (node (ref "U14") (pin "P$7") (pinfunction "Q7_P$7") (pintype "bidirectional"))
    )
    (net (code "42") (name "/UART0_RX") (class "Default")
      (node (ref "U4") (pin "11") (pinfunction "SIN_11") (pintype "bidirectional"))
      (node (ref "U8") (pin "P$12") (pinfunction "R1OUT_P$12") (pintype "bidirectional"))
    )
    (net (code "43") (name "/UART0_TX") (class "Default")
      (node (ref "U4") (pin "13") (pinfunction "SOUT_13") (pintype "bidirectional"))
      (node (ref "U8") (pin "P$11") (pinfunction "T1IN_P$11") (pintype "bidirectional"))
    )
    (net (code "44") (name "/UART1_RX") (class "Default")
      (node (ref "P1") (pin "3") (pinfunction "3_3") (pintype "bidirectional"))
      (node (ref "U16") (pin "11") (pinfunction "SIN_11") (pintype "bidirectional"))
    )
    (net (code "45") (name "/UART1_TX") (class "Default")
      (node (ref "P1") (pin "2") (pinfunction "2_2") (pintype "bidirectional"))
      (node (ref "U16") (pin "13") (pinfunction "SOUT_13") (pintype "bidirectional"))
    )
    (net (code "46") (name "/VCC") (class "Default")
      (node (ref "C1") (pin "2") (pinfunction "2_2") (pintype "bidirectional"))
      (node (ref "C10") (pin "2") (pinfunction "2_2") (pintype "bidirectional"))
      (node (ref "C11") (pin "2") (pinfunction "2_2") (pintype "bidirectional"))
      (node (ref "C14") (pin "2") (pinfunction "2_2") (pintype "bidirectional"))
      (node (ref "C15") (pin "2") (pinfunction "2_2") (pintype "bidirectional"))
      (node (ref "C19") (pin "2") (pinfunction "2_2") (pintype "bidirectional"))
      (node (ref "C2") (pin "2") (pinfunction "2_2") (pintype "bidirectional"))
      (node (ref "C20") (pin "2") (pinfunction "2_2") (pintype "bidirectional"))
      (node (ref "C21") (pin "2") (pinfunction "2_2") (pintype "bidirectional"))
      (node (ref "C23") (pin "2") (pinfunction "2_2") (pintype "bidirectional"))
      (node (ref "C26") (pin "2") (pinfunction "2_2") (pintype "bidirectional"))
      (node (ref "C27") (pin "2") (pinfunction "2_2") (pintype "bidirectional"))
      (node (ref "C5") (pin "2") (pinfunction "2_2") (pintype "bidirectional"))
      (node (ref "C6") (pin "2") (pinfunction "2_2") (pintype "bidirectional"))
      (node (ref "C7") (pin "2") (pinfunction "2_2") (pintype "bidirectional"))
      (node (ref "C8") (pin "2") (pinfunction "2_2") (pintype "bidirectional"))
      (node (ref "C9") (pin "2") (pinfunction "2_2") (pintype "bidirectional"))
      (node (ref "P5") (pin "4") (pinfunction "4_4") (pintype "bidirectional"))
      (node (ref "P6") (pin "6") (pinfunction "6_6") (pintype "bidirectional"))
      (node (ref "R2") (pin "1") (pinfunction "1_1") (pintype "bidirectional"))
      (node (ref "U1") (pin "6") (pinfunction "VCC_6") (pintype "bidirectional"))
      (node (ref "U10") (pin "P$14") (pinfunction "VCC_P$14") (pintype "bidirectional"))
      (node (ref "U11") (pin "P$16") (pinfunction "VCC_P$16") (pintype "bidirectional"))
      (node (ref "U12") (pin "P$14") (pinfunction "VCC_P$14") (pintype "bidirectional"))
      (node (ref "U13") (pin "P$16") (pinfunction "VCC_P$16") (pintype "bidirectional"))
      (node (ref "U14") (pin "P$16") (pinfunction "VCC_P$16") (pintype "bidirectional"))
      (node (ref "U15") (pin "P$20") (pinfunction "VCC_P$20") (pintype "bidirectional"))
      (node (ref "U16") (pin "14") (pinfunction "CS0_14") (pintype "bidirectional"))
      (node (ref "U16") (pin "15") (pinfunction "CS1_15") (pintype "bidirectional"))
      (node (ref "U16") (pin "44") (pinfunction "VCC_44") (pintype "bidirectional"))
      (node (ref "U2") (pin "P$28") (pinfunction "VCC_P$28") (pintype "bidirectional"))
      (node (ref "U3") (pin "P$28") (pinfunction "VCC_P$28") (pintype "bidirectional"))
      (node (ref "U4") (pin "14") (pinfunction "CS0_14") (pintype "bidirectional"))
      (node (ref "U4") (pin "15") (pinfunction "CS1_15") (pintype "bidirectional"))
      (node (ref "U4") (pin "44") (pinfunction "VCC_44") (pintype "bidirectional"))
      (node (ref "U5") (pin "32") (pinfunction "VCC_32") (pintype "bidirectional"))
      (node (ref "U7") (pin "2") (pinfunction "VOUT_2") (pintype "bidirectional"))
      (node (ref "U7") (pin "4") (pinfunction "VOUT_4") (pintype "bidirectional"))
      (node (ref "U8") (pin "P$16") (pinfunction "VCC_P$16") (pintype "bidirectional"))
      (node (ref "U9") (pin "P$14") (pinfunction "VCC_P$14") (pintype "bidirectional"))
      (node (ref "X1") (pin "P$1") (pinfunction "OE_P$1") (pintype "bidirectional"))
      (node (ref "X1") (pin "P$4") (pinfunction "VCC_P$4") (pintype "bidirectional"))
      (node (ref "X2") (pin "P$1") (pinfunction "OE_P$1") (pintype "bidirectional"))
      (node (ref "X2") (pin "P$4") (pinfunction "VCC_P$4") (pintype "bidirectional"))
    )
    (net (code "47") (name "/VIN") (class "Default")
      (node (ref "C3") (pin "2") (pinfunction "2_2") (pintype "bidirectional"))
      (node (ref "C4") (pin "2") (pinfunction "2_2") (pintype "bidirectional"))
      (node (ref "P5") (pin "2") (pinfunction "2_2") (pintype "bidirectional"))
      (node (ref "R1") (pin "1") (pinfunction "1_1") (pintype "bidirectional"))
      (node (ref "S1") (pin "1") (pinfunction "3_1") (pintype "bidirectional"))
      (node (ref "U7") (pin "3") (pinfunction "VIN_3") (pintype "bidirectional"))
    )
    (net (code "48") (name "/~{ADDR15}") (class "Default")
      (node (ref "U3") (pin "P$20") (pinfunction "~{CE}_P$20") (pintype "bidirectional"))
      (node (ref "U9") (pin "P$10") (pinfunction "3B_P$10") (pintype "bidirectional"))
      (node (ref "U9") (pin "P$13") (pinfunction "4B_P$13") (pintype "bidirectional"))
      (node (ref "U9") (pin "P$3") (pinfunction "1Y_P$3") (pintype "bidirectional"))
    )
    (net (code "49") (name "/~{BUSACK}") (class "Default")
      (node (ref "P4") (pin "9") (pinfunction "9_9") (pintype "bidirectional"))
      (node (ref "U1") (pin "20") (pinfunction "~{BUSACK}_20") (pintype "bidirectional"))
    )
    (net (code "50") (name "/~{BUSREQ}") (class "Default")
      (node (ref "P4") (pin "8") (pinfunction "8_8") (pintype "bidirectional"))
      (node (ref "P6") (pin "4") (pinfunction "4_4") (pintype "bidirectional"))
      (node (ref "U1") (pin "22") (pinfunction "~{BUSREQ}_22") (pintype "bidirectional"))
    )
    (net (code "51") (name "/~{HALT}") (class "Default")
      (node (ref "P4") (pin "4") (pinfunction "4_4") (pintype "bidirectional"))
      (node (ref "U1") (pin "14") (pinfunction "~{HALT}_14") (pintype "bidirectional"))
    )
    (net (code "52") (name "/~{INT}") (class "Default")
      (node (ref "P4") (pin "1") (pinfunction "1_1") (pintype "bidirectional"))
      (node (ref "P6") (pin "1") (pinfunction "1_1") (pintype "bidirectional"))
      (node (ref "U1") (pin "12") (pinfunction "~{INT}_12") (pintype "bidirectional"))
      (node (ref "U12") (pin "P$6") (pinfunction "2Y_P$6") (pintype "bidirectional"))
    )
    (net (code "53") (name "/~{IODEV0}") (class "Default")
      (node (ref "U10") (pin "P$9") (pinfunction "3A_P$9") (pintype "bidirectional"))
      (node (ref "U11") (pin "P$15") (pinfunction "Y0_P$15") (pintype "bidirectional"))
    )
    (net (code "54") (name "/~{IODEV1}") (class "Default")
      (node (ref "U11") (pin "P$14") (pinfunction "Y1_P$14") (pintype "bidirectional"))
      (node (ref "U4") (pin "16") (pinfunction "~{CS2}_16") (pintype "bidirectional"))
    )
    (net (code "55") (name "/~{IODEV2}") (class "Default")
      (node (ref "U11") (pin "P$13") (pinfunction "Y2_P$13") (pintype "bidirectional"))
      (node (ref "U16") (pin "16") (pinfunction "~{CS2}_16") (pintype "bidirectional"))
    )
    (net (code "56") (name "/~{IODEV3}") (class "Default")
      (node (ref "U11") (pin "P$12") (pinfunction "Y3_P$12") (pintype "bidirectional"))
    )
    (net (code "57") (name "/~{IODEV4}") (class "Default")
      (node (ref "U11") (pin "P$11") (pinfunction "Y4_P$11") (pintype "bidirectional"))
    )
    (net (code "58") (name "/~{IODEV5}") (class "Default")
      (node (ref "U11") (pin "P$10") (pinfunction "Y5_P$10") (pintype "bidirectional"))
    )
    (net (code "59") (name "/~{IODEV6}") (class "Default")
      (node (ref "U11") (pin "P$9") (pinfunction "Y6_P$9") (pintype "bidirectional"))
    )
    (net (code "60") (name "/~{IODEV7}") (class "Default")
      (node (ref "U11") (pin "P$7") (pinfunction "Y7_P$7") (pintype "bidirectional"))
    )
    (net (code "61") (name "/~{IORQ}") (class "Default")
      (node (ref "P4") (pin "6") (pinfunction "6_6") (pintype "bidirectional"))
      (node (ref "U1") (pin "16") (pinfunction "~{IORQ}_16") (pintype "bidirectional"))
      (node (ref "U11") (pin "P$4") (pinfunction "~{G2A}_P$4") (pintype "bidirectional"))
      (node (ref "U11") (pin "P$5") (pinfunction "~{G2B}_P$5") (pintype "bidirectional"))
    )
    (net (code "62") (name "/~{M1}") (class "Default")
      (node (ref "P4") (pin "12") (pinfunction "12_12") (pintype "bidirectional"))
      (node (ref "U1") (pin "24") (pinfunction "~{M1}_24") (pintype "bidirectional"))
      (node (ref "U11") (pin "P$6") (pinfunction "G1_P$6") (pintype "bidirectional"))
    )
    (net (code "63") (name "/~{MREQ}") (class "Default")
      (node (ref "P4") (pin "5") (pinfunction "5_5") (pintype "bidirectional"))
      (node (ref "U1") (pin "15") (pinfunction "~{MREQ}_15") (pintype "bidirectional"))
    )
    (net (code "64") (name "/~{NMI}") (class "Default")
      (node (ref "P4") (pin "2") (pinfunction "2_2") (pintype "bidirectional"))
      (node (ref "P6") (pin "2") (pinfunction "2_2") (pintype "bidirectional"))
      (node (ref "U1") (pin "13") (pinfunction "~{NMI}_13") (pintype "bidirectional"))
    )
    (net (code "65") (name "/~{RAM_BANK0_CE}") (class "Default")
      (node (ref "U2") (pin "P$20") (pinfunction "~{CE}_P$20") (pintype "bidirectional"))
      (node (ref "U9") (pin "P$11") (pinfunction "4Y_P$11") (pintype "bidirectional"))
    )
    (net (code "66") (name "/~{RD}") (class "Default")
      (node (ref "P4") (pin "11") (pinfunction "11_11") (pintype "bidirectional"))
      (node (ref "U1") (pin "18") (pinfunction "~{RD}_18") (pintype "bidirectional"))
      (node (ref "U16") (pin "24") (pinfunction "~{RD}_24") (pintype "bidirectional"))
      (node (ref "U2") (pin "P$22") (pinfunction "~{OE}_P$22") (pintype "bidirectional"))
      (node (ref "U3") (pin "P$22") (pinfunction "~{OE}_P$22") (pintype "bidirectional"))
      (node (ref "U4") (pin "24") (pinfunction "~{RD}_24") (pintype "bidirectional"))
      (node (ref "U5") (pin "25") (pinfunction "~{OE}_25") (pintype "bidirectional"))
    )
    (net (code "67") (name "/~{RESET}") (class "Default")
      (node (ref "B1") (pin "1") (pinfunction "1_1") (pintype "bidirectional"))
      (node (ref "P4") (pin "7") (pinfunction "7_7") (pintype "bidirectional"))
      (node (ref "P6") (pin "5") (pinfunction "5_5") (pintype "bidirectional"))
      (node (ref "U1") (pin "23") (pinfunction "~{RESET}_23") (pintype "bidirectional"))
      (node (ref "U12") (pin "P$1") (pinfunction "1A_P$1") (pintype "bidirectional"))
      (node (ref "U12") (pin "P$2") (pinfunction "1B_P$2") (pintype "bidirectional"))
      (node (ref "U15") (pin "P$1") (pinfunction "~{MR}_P$1") (pintype "bidirectional"))
    )
    (net (code "68") (name "/~{RFSH}") (class "Default")
      (node (ref "P4") (pin "13") (pinfunction "13_13") (pintype "bidirectional"))
      (node (ref "U1") (pin "25") (pinfunction "~{RFSH}_25") (pintype "bidirectional"))
    )
    (net (code "69") (name "/~{ROM_CE}") (class "Default")
      (node (ref "U5") (pin "23") (pinfunction "~{CE}_23") (pintype "bidirectional"))
      (node (ref "U9") (pin "P$8") (pinfunction "3Y_P$8") (pintype "bidirectional"))
    )
    (net (code "70") (name "/~{ROM_EN}") (class "Default")
      (node (ref "P4") (pin "15") (pinfunction "15_15") (pintype "bidirectional"))
      (node (ref "U15") (pin "P$2") (pinfunction "Q0_P$2") (pintype "bidirectional"))
      (node (ref "U9") (pin "P$12") (pinfunction "4A_P$12") (pintype "bidirectional"))
      (node (ref "U9") (pin "P$4") (pinfunction "2A_P$4") (pintype "bidirectional"))
      (node (ref "U9") (pin "P$5") (pinfunction "2B_P$5") (pintype "bidirectional"))
    )
    (net (code "71") (name "/~{SCR0_CP}") (class "Default")
      (node (ref "U10") (pin "P$8") (pinfunction "3Y_P$8") (pintype "bidirectional"))
      (node (ref "U12") (pin "P$10") (pinfunction "3B_P$10") (pintype "bidirectional"))
      (node (ref "U12") (pin "P$9") (pinfunction "3A_P$9") (pintype "bidirectional"))
    )
    (net (code "72") (name "/~{TIMER_CLR}") (class "Default")
      (node (ref "U13") (pin "P$10") (pinfunction "~{CCLR}_P$10") (pintype "bidirectional"))
      (node (ref "U14") (pin "P$10") (pinfunction "~{CCLR}_P$10") (pintype "bidirectional"))
      (node (ref "U15") (pin "P$6") (pinfunction "Q2_P$6") (pintype "bidirectional"))
    )
    (net (code "73") (name "/~{WAIT}") (class "Default")
      (node (ref "P4") (pin "3") (pinfunction "3_3") (pintype "bidirectional"))
      (node (ref "P6") (pin "3") (pinfunction "3_3") (pintype "bidirectional"))
      (node (ref "U1") (pin "21") (pinfunction "~{WAIT}_21") (pintype "bidirectional"))
    )
    (net (code "74") (name "/~{WR}") (class "Default")
      (node (ref "P4") (pin "10") (pinfunction "10_10") (pintype "bidirectional"))
      (node (ref "U1") (pin "19") (pinfunction "~{WR}_19") (pintype "bidirectional"))
      (node (ref "U10") (pin "P$10") (pinfunction "3B_P$10") (pintype "bidirectional"))
      (node (ref "U16") (pin "20") (pinfunction "~{WR}_20") (pintype "bidirectional"))
      (node (ref "U2") (pin "P$27") (pinfunction "~{WE}_P$27") (pintype "bidirectional"))
      (node (ref "U3") (pin "P$27") (pinfunction "~{WE}_P$27") (pintype "bidirectional"))
      (node (ref "U4") (pin "20") (pinfunction "~{WR}_20") (pintype "bidirectional"))
      (node (ref "U5") (pin "31") (pinfunction "~{WE}_31") (pintype "bidirectional"))
    )
    (net (code "75") (name "GND") (class "Default")
      (node (ref "B1") (pin "2") (pinfunction "2_2") (pintype "bidirectional"))
      (node (ref "C1") (pin "1") (pinfunction "1_1") (pintype "bidirectional"))
      (node (ref "C10") (pin "1") (pinfunction "1_1") (pintype "bidirectional"))
      (node (ref "C11") (pin "1") (pinfunction "1_1") (pintype "bidirectional"))
      (node (ref "C14") (pin "1") (pinfunction "1_1") (pintype "bidirectional"))
      (node (ref "C15") (pin "1") (pinfunction "1_1") (pintype "bidirectional"))
      (node (ref "C19") (pin "1") (pinfunction "1_1") (pintype "bidirectional"))
      (node (ref "C2") (pin "1") (pinfunction "1_1") (pintype "bidirectional"))
      (node (ref "C20") (pin "1") (pinfunction "1_1") (pintype "bidirectional"))
      (node (ref "C21") (pin "1") (pinfunction "1_1") (pintype "bidirectional"))
      (node (ref "C25") (pin "1") (pinfunction "1_1") (pintype "bidirectional"))
      (node (ref "C26") (pin "1") (pinfunction "1_1") (pintype "bidirectional"))
      (node (ref "C27") (pin "1") (pinfunction "1_1") (pintype "bidirectional"))
      (node (ref "C3") (pin "1") (pinfunction "1_1") (pintype "bidirectional"))
      (node (ref "C4") (pin "1") (pinfunction "1_1") (pintype "bidirectional"))
      (node (ref "C5") (pin "1") (pinfunction "1_1") (pintype "bidirectional"))
      (node (ref "C6") (pin "1") (pinfunction "1_1") (pintype "bidirectional"))
      (node (ref "C7") (pin "1") (pinfunction "1_1") (pintype "bidirectional"))
      (node (ref "C8") (pin "1") (pinfunction "1_1") (pintype "bidirectional"))
      (node (ref "C9") (pin "1") (pinfunction "1_1") (pintype "bidirectional"))
      (node (ref "D1") (pin "2") (pinfunction "2_2") (pintype "bidirectional"))
      (node (ref "D2") (pin "2") (pinfunction "2_2") (pintype "bidirectional"))
      (node (ref "J1") (pin "GND") (pinfunction "GND_GND") (pintype "bidirectional"))
      (node (ref "J1") (pin "GNDBREAK") (pinfunction "GNDBREAK_GNDBREAK") (pintype "bidirectional"))
      (node (ref "J2") (pin "5") (pinfunction "GND_5") (pintype "bidirectional"))
      (node (ref "P1") (pin "1") (pinfunction "1_1") (pintype "bidirectional"))
      (node (ref "P4") (pin "16") (pinfunction "16_16") (pintype "bidirectional"))
      (node (ref "P5") (pin "1") (pinfunction "1_1") (pintype "bidirectional"))
      (node (ref "P5") (pin "3") (pinfunction "3_3") (pintype "bidirectional"))
      (node (ref "U1") (pin "26") (pinfunction "GND_26") (pintype "bidirectional"))
      (node (ref "U10") (pin "P$7") (pinfunction "GND_P$7") (pintype "bidirectional"))
      (node (ref "U11") (pin "P$8") (pinfunction "GND_P$8") (pintype "bidirectional"))
      (node (ref "U12") (pin "P$7") (pinfunction "GND_P$7") (pintype "bidirectional"))
      (node (ref "U13") (pin "P$12") (pinfunction "~{CCKEN}_P$12") (pintype "bidirectional"))
      (node (ref "U13") (pin "P$14") (pinfunction "~{OE}_P$14") (pintype "bidirectional"))
      (node (ref "U13") (pin "P$8") (pinfunction "GND_P$8") (pintype "bidirectional"))
      (node (ref "U14") (pin "P$14") (pinfunction "~{OE}_P$14") (pintype "bidirectional"))
      (node (ref "U14") (pin "P$8") (pinfunction "GND_P$8") (pintype "bidirectional"))
      (node (ref "U15") (pin "P$10") (pinfunction "GND_P$10") (pintype "bidirectional"))
      (node (ref "U16") (pin "21") (pinfunction "WR_21") (pintype "bidirectional"))
      (node (ref "U16") (pin "22") (pinfunction "GND_22") (pintype "bidirectional"))
      (node (ref "U16") (pin "25") (pinfunction "RD_25") (pintype "bidirectional"))
      (node (ref "U16") (pin "28") (pinfunction "~{ADS}_28") (pintype "bidirectional"))
      (node (ref "U2") (pin "P$14") (pinfunction "GND_P$14") (pintype "bidirectional"))
      (node (ref "U3") (pin "P$14") (pinfunction "GND_P$14") (pintype "bidirectional"))
      (node (ref "U4") (pin "21") (pinfunction "WR_21") (pintype "bidirectional"))
      (node (ref "U4") (pin "22") (pinfunction "GND_22") (pintype "bidirectional"))
      (node (ref "U4") (pin "25") (pinfunction "RD_25") (pintype "bidirectional"))
      (node (ref "U4") (pin "28") (pinfunction "~{ADS}_28") (pintype "bidirectional"))
      (node (ref "U5") (pin "16") (pinfunction "GND_16") (pintype "bidirectional"))
      (node (ref "U7") (pin "1") (pinfunction "GND_1") (pintype "bidirectional"))
      (node (ref "U8") (pin "P$15") (pinfunction "GND_P$15") (pintype "bidirectional"))
      (node (ref "U9") (pin "P$7") (pinfunction "GND_P$7") (pintype "bidirectional"))
      (node (ref "X1") (pin "P$2") (pinfunction "GND_P$2") (pintype "bidirectional"))
      (node (ref "X2") (pin "P$2") (pinfunction "GND_P$2") (pintype "bidirectional"))
    )
    (net (code "76") (name "Net-(D1-Pad1)") (class "Default")
      (node (ref "D1") (pin "1") (pinfunction "1_1") (pintype "bidirectional"))
      (node (ref "R2") (pin "2") (pinfunction "2_2") (pintype "bidirectional"))
    )
    (net (code "77") (name "Net-(D2-Pad1)") (class "Default")
      (node (ref "D2") (pin "1") (pinfunction "1_1") (pintype "bidirectional"))
      (node (ref "R1") (pin "2") (pinfunction "2_2") (pintype "bidirectional"))
    )
    (net (code "78") (name "Net-(J2-RXD)") (class "Default")
      (node (ref "J2") (pin "2") (pinfunction "RXD_2") (pintype "bidirectional"))
      (node (ref "U8") (pin "P$13") (pinfunction "R1IN_P$13") (pintype "bidirectional"))
    )
    (net (code "79") (name "Net-(J2-TXD)") (class "Default")
      (node (ref "J2") (pin "3") (pinfunction "TXD_3") (pintype "bidirectional"))
      (node (ref "U8") (pin "P$14") (pinfunction "T1OUT_P$14") (pintype "bidirectional"))
    )
    (net (code "80") (name "Net-(S1-1)") (class "Default")
      (node (ref "J1") (pin "PWR") (pinfunction "PWR_PWR") (pintype "bidirectional"))
      (node (ref "S1") (pin "2") (pinfunction "1_2") (pintype "bidirectional"))
    )
    (net (code "81") (name "Net-(U8-C1+)") (class "Default")
      (node (ref "C22") (pin "2") (pinfunction "2_2") (pintype "bidirectional"))
      (node (ref "U8") (pin "P$1") (pinfunction "C1+_P$1") (pintype "bidirectional"))
    )
    (net (code "82") (name "Net-(U8-C1-)") (class "Default")
      (node (ref "C22") (pin "1") (pinfunction "1_1") (pintype "bidirectional"))
      (node (ref "U8") (pin "P$3") (pinfunction "C1-_P$3") (pintype "bidirectional"))
    )
    (net (code "83") (name "Net-(U8-C2+)") (class "Default")
      (node (ref "C24") (pin "2") (pinfunction "2_2") (pintype "bidirectional"))
      (node (ref "U8") (pin "P$4") (pinfunction "C2+_P$4") (pintype "bidirectional"))
    )
    (net (code "84") (name "Net-(U8-C2-)") (class "Default")
      (node (ref "C24") (pin "1") (pinfunction "1_1") (pintype "bidirectional"))
      (node (ref "U8") (pin "P$5") (pinfunction "C2-_P$5") (pintype "bidirectional"))
    )
    (net (code "85") (name "Net-(U8-VS+)") (class "Default")
      (node (ref "C23") (pin "1") (pinfunction "1_1") (pintype "bidirectional"))
      (node (ref "U8") (pin "P$2") (pinfunction "VS+_P$2") (pintype "bidirectional"))
    )
    (net (code "86") (name "Net-(U8-VS-)") (class "Default")
      (node (ref "C25") (pin "2") (pinfunction "2_2") (pintype "bidirectional"))
      (node (ref "U8") (pin "P$6") (pinfunction "VS-_P$6") (pintype "bidirectional"))
    )
    (net (code "87") (name "Net-(U13-~{RCO})") (class "Default")
      (node (ref "U13") (pin "P$9") (pinfunction "~{RCO}_P$9") (pintype "bidirectional"))
      (node (ref "U14") (pin "P$12") (pinfunction "~{CCKEN}_P$12") (pintype "bidirectional"))
    )
    (net (code "88") (name "unconnected-(J2-CTS-Pad8)") (class "Default")
      (node (ref "J2") (pin "8") (pinfunction "CTS_8") (pintype "bidirectional"))
    )
    (net (code "89") (name "unconnected-(J2-DCD-Pad1)") (class "Default")
      (node (ref "J2") (pin "1") (pinfunction "DCD_1") (pintype "bidirectional"))
    )
    (net (code "90") (name "unconnected-(J2-DSR-Pad6)") (class "Default")
      (node (ref "J2") (pin "6") (pinfunction "DSR_6") (pintype "bidirectional"))
    )
    (net (code "91") (name "unconnected-(J2-DTR-Pad4)") (class "Default")
      (node (ref "J2") (pin "4") (pinfunction "DTR_4") (pintype "bidirectional"))
    )
    (net (code "92") (name "unconnected-(J2-RI-Pad9)") (class "Default")
      (node (ref "J2") (pin "9") (pinfunction "RI_9") (pintype "bidirectional"))
    )
    (net (code "93") (name "unconnected-(J2-RTS-Pad7)") (class "Default")
      (node (ref "J2") (pin "7") (pinfunction "RTS_7") (pintype "bidirectional"))
    )
    (net (code "94") (name "unconnected-(S1-2-Pad3)") (class "Default")
      (node (ref "S1") (pin "3") (pinfunction "2_3") (pintype "bidirectional"))
    )
    (net (code "95") (name "unconnected-(U1-NC-Pad11)") (class "Default")
      (node (ref "U1") (pin "11") (pinfunction "NC_11") (pintype "bidirectional"))
    )
    (net (code "96") (name "unconnected-(U1-NC-Pad17)") (class "Default")
      (node (ref "U1") (pin "17") (pinfunction "NC_17") (pintype "bidirectional"))
    )
    (net (code "97") (name "unconnected-(U1-NC-Pad33)") (class "Default")
      (node (ref "U1") (pin "33") (pinfunction "NC_33") (pintype "bidirectional"))
    )
    (net (code "98") (name "unconnected-(U1-NC-Pad39)") (class "Default")
      (node (ref "U1") (pin "39") (pinfunction "NC_39") (pintype "bidirectional"))
    )
    (net (code "99") (name "unconnected-(U4-DDIS-Pad26)") (class "Default")
      (node (ref "U4") (pin "26") (pinfunction "DDIS_26") (pintype "bidirectional"))
    )
    (net (code "100") (name "unconnected-(U4-XOUT-Pad19)") (class "Default")
      (node (ref "U4") (pin "19") (pinfunction "XOUT_19") (pintype "bidirectional"))
    )
    (net (code "101") (name "unconnected-(U4-~{CTS}-Pad40)") (class "Default")
      (node (ref "U4") (pin "40") (pinfunction "~{CTS}_40") (pintype "bidirectional"))
    )
    (net (code "102") (name "unconnected-(U4-~{DCD}-Pad42)") (class "Default")
      (node (ref "U4") (pin "42") (pinfunction "~{DCD}_42") (pintype "bidirectional"))
    )
    (net (code "103") (name "unconnected-(U4-~{DSR}-Pad41)") (class "Default")
      (node (ref "U4") (pin "41") (pinfunction "~{DSR}_41") (pintype "bidirectional"))
    )
    (net (code "104") (name "unconnected-(U4-~{DTR}-Pad37)") (class "Default")
      (node (ref "U4") (pin "37") (pinfunction "~{DTR}_37") (pintype "bidirectional"))
    )
    (net (code "105") (name "unconnected-(U4-~{OUT1}-Pad38)") (class "Default")
      (node (ref "U4") (pin "38") (pinfunction "~{OUT1}_38") (pintype "bidirectional"))
    )
    (net (code "106") (name "unconnected-(U4-~{OUT2}-Pad35)") (class "Default")
      (node (ref "U4") (pin "35") (pinfunction "~{OUT2}_35") (pintype "bidirectional"))
    )
    (net (code "107") (name "unconnected-(U4-~{RI}-Pad43)") (class "Default")
      (node (ref "U4") (pin "43") (pinfunction "~{RI}_43") (pintype "bidirectional"))
    )
    (net (code "108") (name "unconnected-(U4-~{RTS}-Pad36)") (class "Default")
      (node (ref "U4") (pin "36") (pinfunction "~{RTS}_36") (pintype "bidirectional"))
    )
    (net (code "109") (name "unconnected-(U4-~{RXRDY}-Pad32)") (class "Default")
      (node (ref "U4") (pin "32") (pinfunction "~{RXRDY}_32") (pintype "bidirectional"))
    )
    (net (code "110") (name "unconnected-(U4-~{TXRDY}-Pad27)") (class "Default")
      (node (ref "U4") (pin "27") (pinfunction "~{TXRDY}_27") (pintype "bidirectional"))
    )
    (net (code "111") (name "unconnected-(U8-R2IN-PadP$8)") (class "Default")
      (node (ref "U8") (pin "P$8") (pinfunction "R2IN_P$8") (pintype "bidirectional"))
    )
    (net (code "112") (name "unconnected-(U8-R2OUT-PadP$9)") (class "Default")
      (node (ref "U8") (pin "P$9") (pinfunction "R2OUT_P$9") (pintype "bidirectional"))
    )
    (net (code "113") (name "unconnected-(U8-T2IN-PadP$10)") (class "Default")
      (node (ref "U8") (pin "P$10") (pinfunction "T2IN_P$10") (pintype "bidirectional"))
    )
    (net (code "114") (name "unconnected-(U8-T2OUT-PadP$7)") (class "Default")
      (node (ref "U8") (pin "P$7") (pinfunction "T2OUT_P$7") (pintype "bidirectional"))
    )
    (net (code "115") (name "unconnected-(U10-4A-PadP$12)") (class "Default")
      (node (ref "U10") (pin "P$12") (pinfunction "4A_P$12") (pintype "bidirectional"))
    )
    (net (code "116") (name "unconnected-(U10-4B-PadP$13)") (class "Default")
      (node (ref "U10") (pin "P$13") (pinfunction "4B_P$13") (pintype "bidirectional"))
    )
    (net (code "117") (name "unconnected-(U10-4Y-PadP$11)") (class "Default")
      (node (ref "U10") (pin "P$11") (pinfunction "4Y_P$11") (pintype "bidirectional"))
    )
    (net (code "118") (name "unconnected-(U12-4A-PadP$12)") (class "Default")
      (node (ref "U12") (pin "P$12") (pinfunction "4A_P$12") (pintype "bidirectional"))
    )
    (net (code "119") (name "unconnected-(U12-4B-PadP$13)") (class "Default")
      (node (ref "U12") (pin "P$13") (pinfunction "4B_P$13") (pintype "bidirectional"))
    )
    (net (code "120") (name "unconnected-(U12-4Y-PadP$11)") (class "Default")
      (node (ref "U12") (pin "P$11") (pinfunction "4Y_P$11") (pintype "bidirectional"))
    )
    (net (code "121") (name "unconnected-(U13-Q0-PadP$15)") (class "Default")
      (node (ref "U13") (pin "P$15") (pinfunction "Q0_P$15") (pintype "bidirectional"))
    )
    (net (code "122") (name "unconnected-(U13-Q1-PadP$1)") (class "Default")
      (node (ref "U13") (pin "P$1") (pinfunction "Q1_P$1") (pintype "bidirectional"))
    )
    (net (code "123") (name "unconnected-(U13-Q2-PadP$2)") (class "Default")
      (node (ref "U13") (pin "P$2") (pinfunction "Q2_P$2") (pintype "bidirectional"))
    )
    (net (code "124") (name "unconnected-(U13-Q3-PadP$3)") (class "Default")
      (node (ref "U13") (pin "P$3") (pinfunction "Q3_P$3") (pintype "bidirectional"))
    )
    (net (code "125") (name "unconnected-(U13-Q4-PadP$4)") (class "Default")
      (node (ref "U13") (pin "P$4") (pinfunction "Q4_P$4") (pintype "bidirectional"))
    )
    (net (code "126") (name "unconnected-(U13-Q5-PadP$5)") (class "Default")
      (node (ref "U13") (pin "P$5") (pinfunction "Q5_P$5") (pintype "bidirectional"))
    )
    (net (code "127") (name "unconnected-(U13-Q6-PadP$6)") (class "Default")
      (node (ref "U13") (pin "P$6") (pinfunction "Q6_P$6") (pintype "bidirectional"))
    )
    (net (code "128") (name "unconnected-(U13-Q7-PadP$7)") (class "Default")
      (node (ref "U13") (pin "P$7") (pinfunction "Q7_P$7") (pintype "bidirectional"))
    )
    (net (code "129") (name "unconnected-(U14-Q0-PadP$15)") (class "Default")
      (node (ref "U14") (pin "P$15") (pinfunction "Q0_P$15") (pintype "bidirectional"))
    )
    (net (code "130") (name "unconnected-(U14-Q1-PadP$1)") (class "Default")
      (node (ref "U14") (pin "P$1") (pinfunction "Q1_P$1") (pintype "bidirectional"))
    )
    (net (code "131") (name "unconnected-(U14-Q2-PadP$2)") (class "Default")
      (node (ref "U14") (pin "P$2") (pinfunction "Q2_P$2") (pintype "bidirectional"))
    )
    (net (code "132") (name "unconnected-(U14-Q3-PadP$3)") (class "Default")
      (node (ref "U14") (pin "P$3") (pinfunction "Q3_P$3") (pintype "bidirectional"))
    )
    (net (code "133") (name "unconnected-(U14-Q4-PadP$4)") (class "Default")
      (node (ref "U14") (pin "P$4") (pinfunction "Q4_P$4") (pintype "bidirectional"))
    )
    (net (code "134") (name "unconnected-(U14-Q5-PadP$5)") (class "Default")
      (node (ref "U14") (pin "P$5") (pinfunction "Q5_P$5") (pintype "bidirectional"))
    )
    (net (code "135") (name "unconnected-(U14-Q6-PadP$6)") (class "Default")
      (node (ref "U14") (pin "P$6") (pinfunction "Q6_P$6") (pintype "bidirectional"))
    )
    (net (code "136") (name "unconnected-(U14-~{RCO}-PadP$9)") (class "Default")
      (node (ref "U14") (pin "P$9") (pinfunction "~{RCO}_P$9") (pintype "bidirectional"))
    )
    (net (code "137") (name "unconnected-(U15-Q3-PadP$9)") (class "Default")
      (node (ref "U15") (pin "P$9") (pinfunction "Q3_P$9") (pintype "bidirectional"))
    )
    (net (code "138") (name "unconnected-(U15-Q4-PadP$12)") (class "Default")
      (node (ref "U15") (pin "P$12") (pinfunction "Q4_P$12") (pintype "bidirectional"))
    )
    (net (code "139") (name "unconnected-(U15-Q5-PadP$15)") (class "Default")
      (node (ref "U15") (pin "P$15") (pinfunction "Q5_P$15") (pintype "bidirectional"))
    )
    (net (code "140") (name "unconnected-(U15-Q6-PadP$16)") (class "Default")
      (node (ref "U15") (pin "P$16") (pinfunction "Q6_P$16") (pintype "bidirectional"))
    )
    (net (code "141") (name "unconnected-(U15-Q7-PadP$19)") (class "Default")
      (node (ref "U15") (pin "P$19") (pinfunction "Q7_P$19") (pintype "bidirectional"))
    )
    (net (code "142") (name "unconnected-(U16-DDIS-Pad26)") (class "Default")
      (node (ref "U16") (pin "26") (pinfunction "DDIS_26") (pintype "bidirectional"))
    )
    (net (code "143") (name "unconnected-(U16-XOUT-Pad19)") (class "Default")
      (node (ref "U16") (pin "19") (pinfunction "XOUT_19") (pintype "bidirectional"))
    )
    (net (code "144") (name "unconnected-(U16-~{CTS}-Pad40)") (class "Default")
      (node (ref "U16") (pin "40") (pinfunction "~{CTS}_40") (pintype "bidirectional"))
    )
    (net (code "145") (name "unconnected-(U16-~{DCD}-Pad42)") (class "Default")
      (node (ref "U16") (pin "42") (pinfunction "~{DCD}_42") (pintype "bidirectional"))
    )
    (net (code "146") (name "unconnected-(U16-~{DSR}-Pad41)") (class "Default")
      (node (ref "U16") (pin "41") (pinfunction "~{DSR}_41") (pintype "bidirectional"))
    )
    (net (code "147") (name "unconnected-(U16-~{DTR}-Pad37)") (class "Default")
      (node (ref "U16") (pin "37") (pinfunction "~{DTR}_37") (pintype "bidirectional"))
    )
    (net (code "148") (name "unconnected-(U16-~{OUT1}-Pad38)") (class "Default")
      (node (ref "U16") (pin "38") (pinfunction "~{OUT1}_38") (pintype "bidirectional"))
    )
    (net (code "149") (name "unconnected-(U16-~{OUT2}-Pad35)") (class "Default")
      (node (ref "U16") (pin "35") (pinfunction "~{OUT2}_35") (pintype "bidirectional"))
    )
    (net (code "150") (name "unconnected-(U16-~{RI}-Pad43)") (class "Default")
      (node (ref "U16") (pin "43") (pinfunction "~{RI}_43") (pintype "bidirectional"))
    )
    (net (code "151") (name "unconnected-(U16-~{RTS}-Pad36)") (class "Default")
      (node (ref "U16") (pin "36") (pinfunction "~{RTS}_36") (pintype "bidirectional"))
    )
    (net (code "152") (name "unconnected-(U16-~{RXRDY}-Pad32)") (class "Default")
      (node (ref "U16") (pin "32") (pinfunction "~{RXRDY}_32") (pintype "bidirectional"))
    )
    (net (code "153") (name "unconnected-(U16-~{TXRDY}-Pad27)") (class "Default")
      (node (ref "U16") (pin "27") (pinfunction "~{TXRDY}_27") (pintype "bidirectional"))
    )
  )
)
